# controller_rev4_3_flat.net
KiCad netlist of a schematic drawn in EAGLE
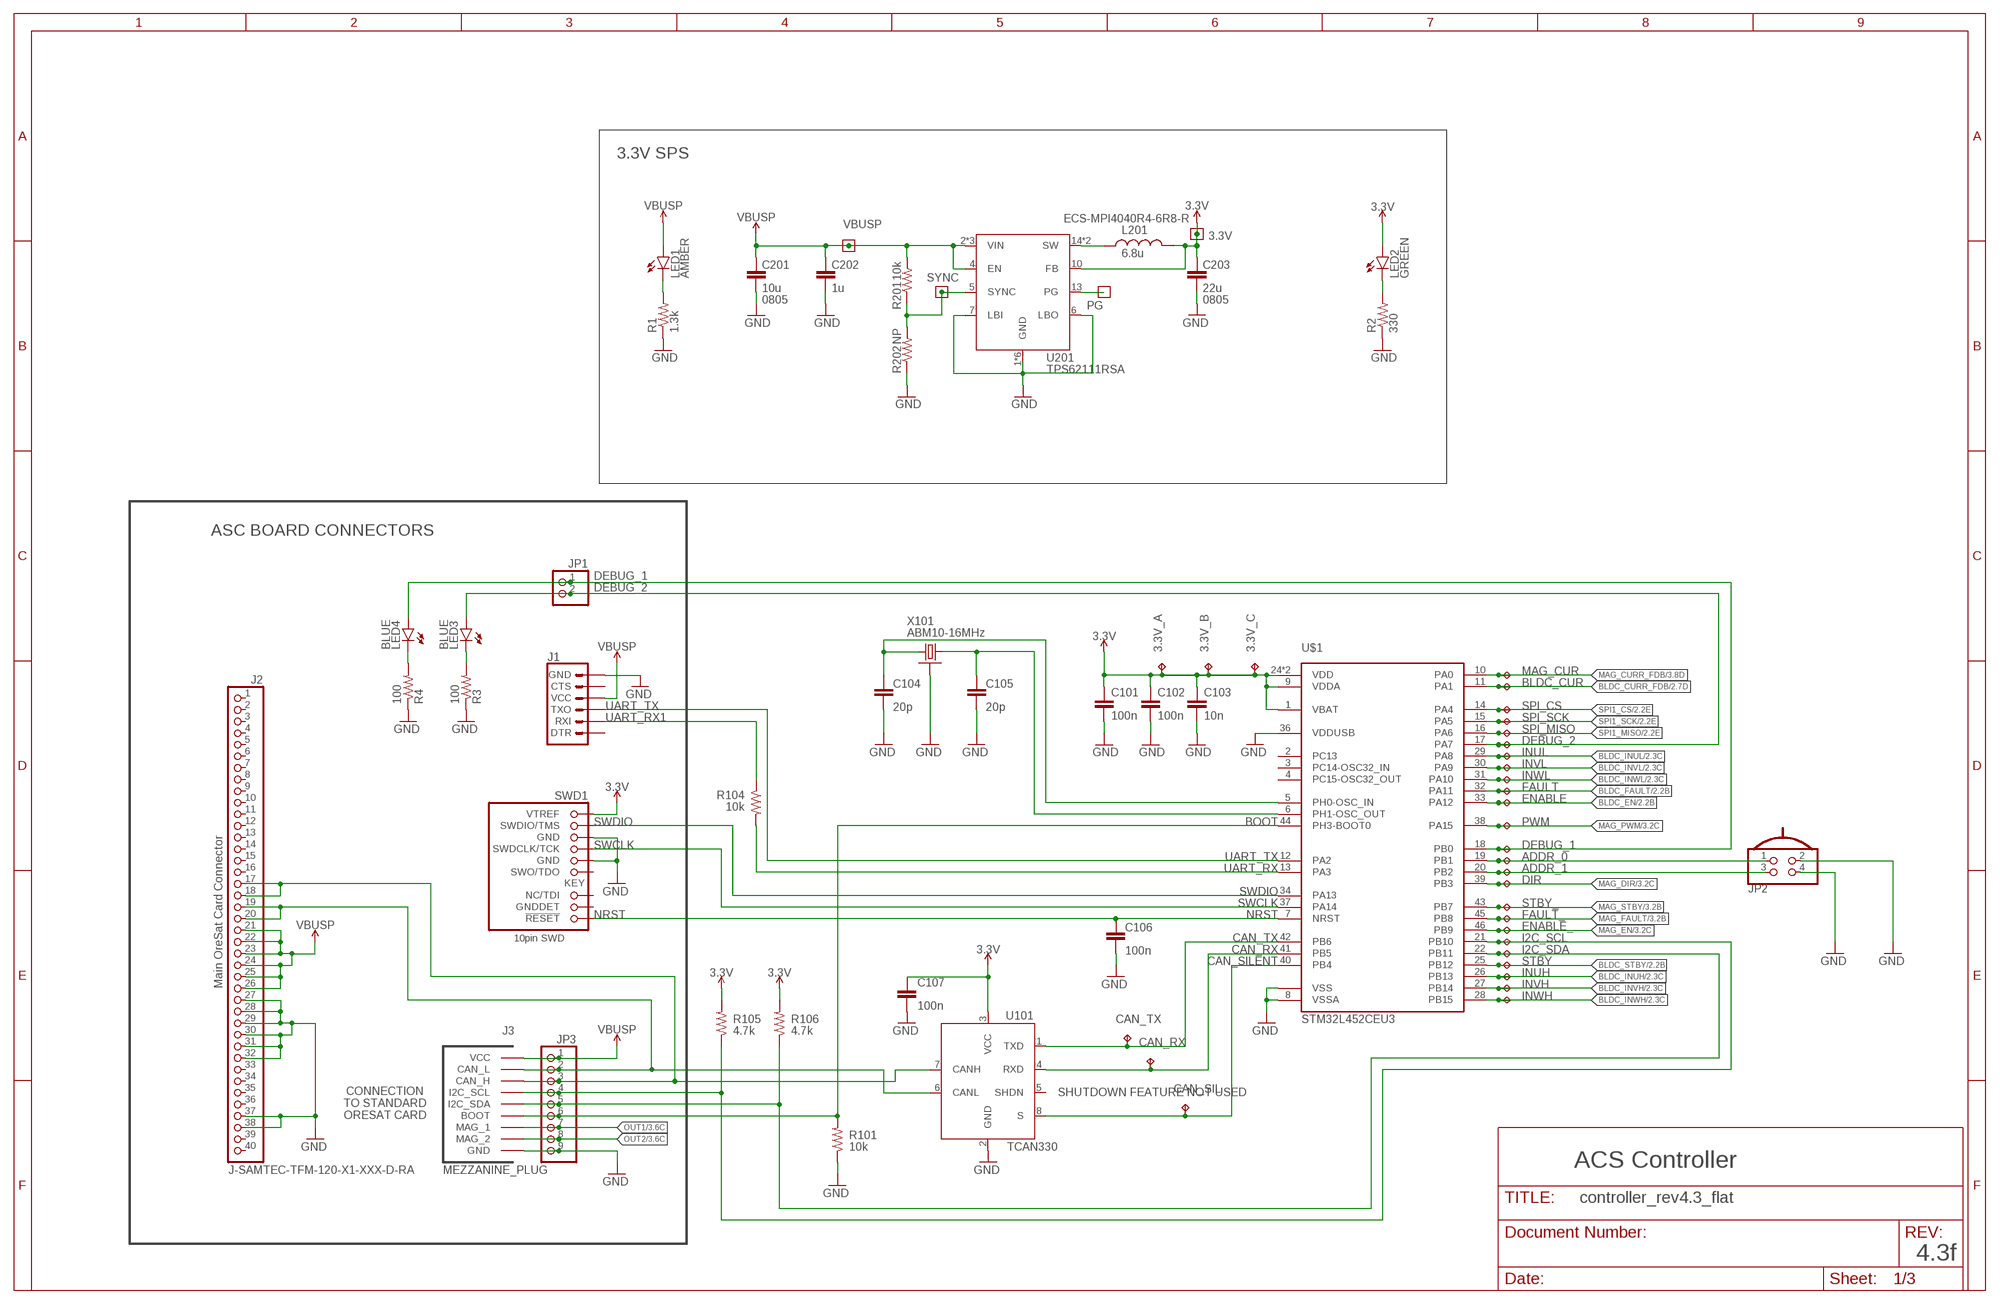
[diagram p0: schematic, sheet 1]
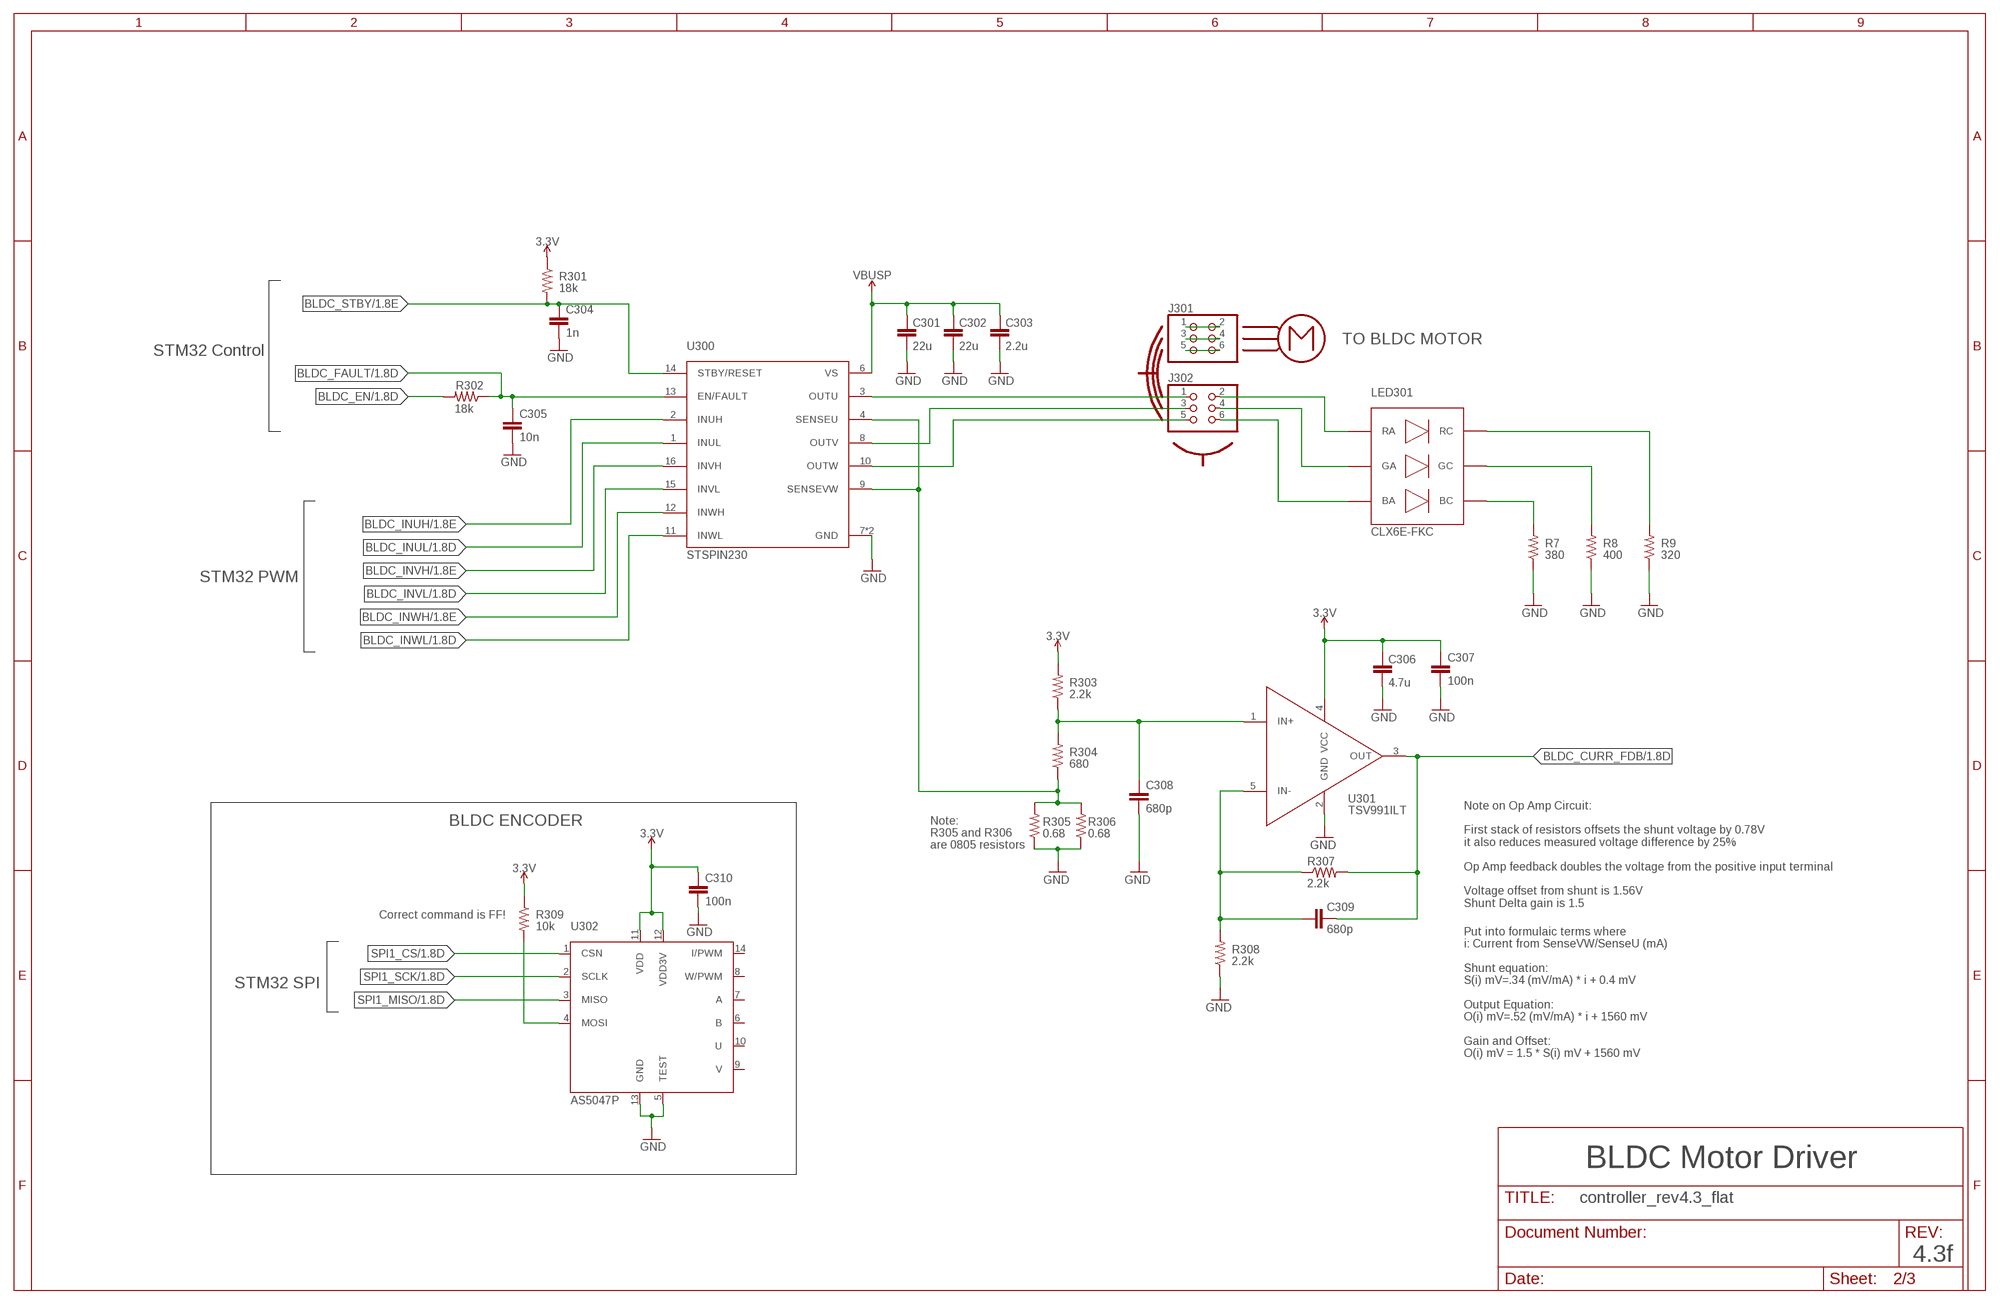
[diagram p1: schematic, sheet 2]
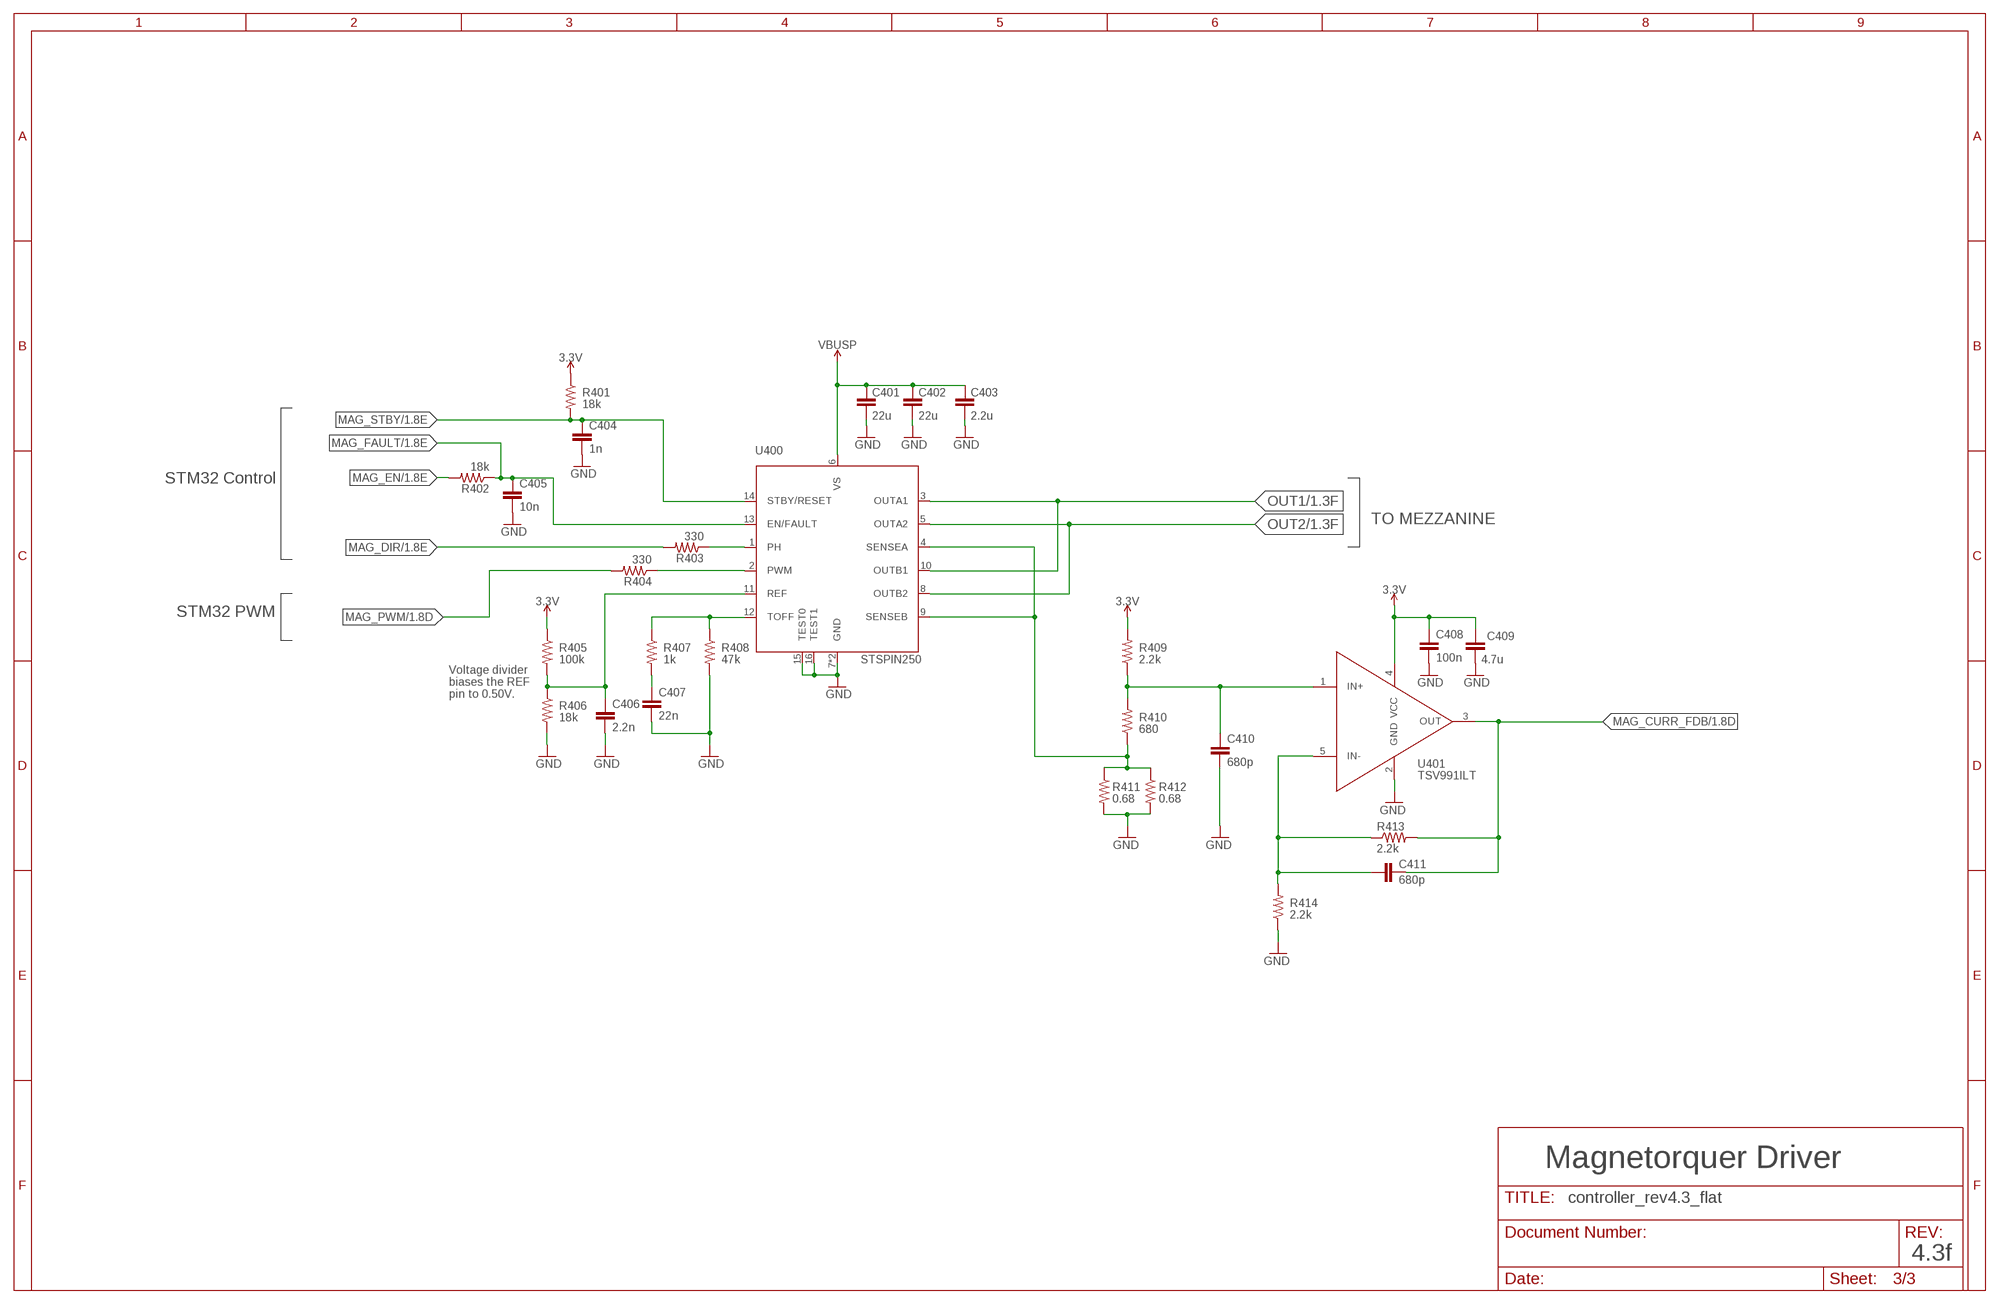
[diagram p2: schematic, sheet 3]

(export (version "E")
  (design (tool "Eeschema 10.0.6"))
  (components
    (comp (ref "3.3V")
      (value "TEST-POINT-LARGE-SQUARE")
      (footprint "eagle-import:1X01")
      (libsource (lib "eagle-import") (part "TEST-POINT-LARGE-SQUARE"))
    )
    (comp (ref "3.3V_A")
      (value "TEST-POINT-LARGE")
      (footprint "eagle-import:1X01")
      (libsource (lib "eagle-import") (part "TEST-POINT-LARGE"))
    )
    (comp (ref "3.3V_B")
      (value "TEST-POINT-LARGE")
      (footprint "eagle-import:1X01")
      (libsource (lib "eagle-import") (part "TEST-POINT-LARGE"))
    )
    (comp (ref "3.3V_C")
      (value "TEST-POINT-LARGE")
      (footprint "eagle-import:1X01")
      (libsource (lib "eagle-import") (part "TEST-POINT-LARGE"))
    )
    (comp (ref "ADDR_0")
      (value "TEST-POINT-LARGE")
      (footprint "eagle-import:1X01")
      (libsource (lib "eagle-import") (part "TEST-POINT-LARGE"))
    )
    (comp (ref "ADDR_1")
      (value "TEST-POINT-LARGE")
      (footprint "eagle-import:1X01")
      (libsource (lib "eagle-import") (part "TEST-POINT-LARGE"))
    )
    (comp (ref "BLDC_CUR")
      (value "TEST-POINT-LARGE")
      (footprint "eagle-import:1X01")
      (libsource (lib "eagle-import") (part "TEST-POINT-LARGE"))
    )
    (comp (ref "C101")
      (value "100n")
      (footprint "eagle-import:.0402-B-NOSILK")
      (fields (field (name "MFR") "Samsung") (field (name "MPN") "CL05B104KO5NNNC"))
      (libsource (lib "eagle-import") (part "rcl_custom_C-EU0402-B-NOSILK"))
    )
    (comp (ref "C102")
      (value "100n")
      (footprint "eagle-import:.0402-B-NOSILK")
      (fields (field (name "MFR") "Samsung") (field (name "MPN") "CL05B104KO5NNNC"))
      (libsource (lib "eagle-import") (part "rcl_custom_C-EU0402-B-NOSILK"))
    )
    (comp (ref "C103")
      (value "10n")
      (footprint "eagle-import:.0402-B-NOSILK")
      (fields (field (name "MFR") "Samsung") (field (name "MPN") "CL05B104KO5NNNC"))
      (libsource (lib "eagle-import") (part "rcl_custom_C-EU0402-B-NOSILK"))
    )
    (comp (ref "C104")
      (value "20p")
      (footprint "eagle-import:.0402-B-NOSILK")
      (fields (field (name "MFR") "Samsung") (field (name "MPN") "CL05C200JB51PNC"))
      (libsource (lib "eagle-import") (part "rcl_custom_C-EU0402-B-NOSILK"))
    )
    (comp (ref "C105")
      (value "20p")
      (footprint "eagle-import:.0402-B-NOSILK")
      (fields (field (name "MFR") "Samsung") (field (name "MPN") "CL05C200JB51PNC"))
      (libsource (lib "eagle-import") (part "rcl_custom_C-EU0402-B-NOSILK"))
    )
    (comp (ref "C106")
      (value "100n")
      (footprint "eagle-import:.0402-B-NOSILK")
      (fields (field (name "MFR") "Samsung") (field (name "MPN") "CL05C200JB51PNC"))
      (libsource (lib "eagle-import") (part "rcl_custom_C-EU0402-B-NOSILK"))
    )
    (comp (ref "C107")
      (value "100n")
      (footprint "eagle-import:.0402-B-NOSILK")
      (fields (field (name "MFR") "Samsung") (field (name "MPN") "CL05B104KO5NNNC"))
      (libsource (lib "eagle-import") (part "rcl_custom_C-EU0402-B-NOSILK"))
    )
    (comp (ref "C201")
      (value "10u")
      (footprint "eagle-import:.0805-B-NOSILK")
      (fields (field (name "MFR") "Samsung") (field (name "MPN") "CL21B106KOQNNNG"))
      (libsource (lib "eagle-import") (part "C-EU0805-B-NOSILK"))
    )
    (comp (ref "C202")
      (value "1u")
      (footprint "eagle-import:.0603-C-NOSILK")
      (fields (field (name "MFR") "Yageo") (field (name "MPN") "CC0603KRX5R7BB105"))
      (libsource (lib "eagle-import") (part "C-EU0603-C-NOSILK"))
    )
    (comp (ref "C203")
      (value "22u")
      (footprint "eagle-import:.0805-B-NOSILK")
      (fields (field (name "MFR") "Murata") (field (name "MPN") "GRM21BD71A226ME44L"))
      (libsource (lib "eagle-import") (part "C-EU0805-B-NOSILK"))
    )
    (comp (ref "CAN_RX")
      (value "TEST-POINT-LARGE")
      (footprint "eagle-import:1X01")
      (libsource (lib "eagle-import") (part "TEST-POINT-LARGE"))
    )
    (comp (ref "CAN_SIL")
      (value "TEST-POINT-LARGE")
      (footprint "eagle-import:1X01")
      (libsource (lib "eagle-import") (part "TEST-POINT-LARGE"))
    )
    (comp (ref "CAN_TX")
      (value "TEST-POINT-LARGE")
      (footprint "eagle-import:1X01")
      (libsource (lib "eagle-import") (part "TEST-POINT-LARGE"))
    )
    (comp (ref "DEBUG_1")
      (value "TEST-POINT-LARGE")
      (footprint "eagle-import:1X01")
      (libsource (lib "eagle-import") (part "TEST-POINT-LARGE"))
    )
    (comp (ref "DEBUG_2")
      (value "TEST-POINT-LARGE")
      (footprint "eagle-import:1X01")
      (libsource (lib "eagle-import") (part "TEST-POINT-LARGE"))
    )
    (comp (ref "DIR")
      (value "TEST-POINT-LARGE")
      (footprint "eagle-import:1X01")
      (libsource (lib "eagle-import") (part "TEST-POINT-LARGE"))
    )
    (comp (ref "ENABLE")
      (value "TEST-POINT-LARGE")
      (footprint "eagle-import:1X01")
      (libsource (lib "eagle-import") (part "TEST-POINT-LARGE"))
    )
    (comp (ref "ENABLE_")
      (value "TEST-POINT-LARGE")
      (footprint "eagle-import:1X01")
      (libsource (lib "eagle-import") (part "TEST-POINT-LARGE"))
    )
    (comp (ref "FAULT")
      (value "TEST-POINT-LARGE")
      (footprint "eagle-import:1X01")
      (libsource (lib "eagle-import") (part "TEST-POINT-LARGE"))
    )
    (comp (ref "FAULT_")
      (value "TEST-POINT-LARGE")
      (footprint "eagle-import:1X01")
      (libsource (lib "eagle-import") (part "TEST-POINT-LARGE"))
    )
    (comp (ref "I2C_SCL")
      (value "TEST-POINT-LARGE")
      (footprint "eagle-import:1X01")
      (libsource (lib "eagle-import") (part "TEST-POINT-LARGE"))
    )
    (comp (ref "I2C_SDA")
      (value "TEST-POINT-LARGE")
      (footprint "eagle-import:1X01")
      (libsource (lib "eagle-import") (part "TEST-POINT-LARGE"))
    )
    (comp (ref "INUH")
      (value "TEST-POINT-LARGE")
      (footprint "eagle-import:1X01")
      (libsource (lib "eagle-import") (part "TEST-POINT-LARGE"))
    )
    (comp (ref "INUL")
      (value "TEST-POINT-LARGE")
      (footprint "eagle-import:1X01")
      (libsource (lib "eagle-import") (part "TEST-POINT-LARGE"))
    )
    (comp (ref "INVH")
      (value "TEST-POINT-LARGE")
      (footprint "eagle-import:1X01")
      (libsource (lib "eagle-import") (part "TEST-POINT-LARGE"))
    )
    (comp (ref "INVL")
      (value "TEST-POINT-LARGE")
      (footprint "eagle-import:1X01")
      (libsource (lib "eagle-import") (part "TEST-POINT-LARGE"))
    )
    (comp (ref "INWH")
      (value "TEST-POINT-LARGE")
      (footprint "eagle-import:1X01")
      (libsource (lib "eagle-import") (part "TEST-POINT-LARGE"))
    )
    (comp (ref "INWL")
      (value "TEST-POINT-LARGE")
      (footprint "eagle-import:1X01")
      (libsource (lib "eagle-import") (part "TEST-POINT-LARGE"))
    )
    (comp (ref "J1")
      (value "6_PIN_SERIAL_TARGETSILK")
      (footprint "eagle-import:6_PIN_SERIAL_TARGET_SIDE_W_SILK")
      (libsource (lib "eagle-import") (part "6_PIN_SERIAL_TARGETSILK"))
    )
    (comp (ref "J2")
      (value "J-SAMTEC-TFM-120-X1-XXX-D-RA")
      (footprint "eagle-import:J-SAMTEC-TFM-120-X1-XXX-D-RA")
      (description "90 degree 40 pos conn header")
      (fields (field (name "MFG") "Samtec Inc."))
      (libsource (lib "eagle-import") (part "J-SAMTEC-TFM-120-X1-XXX-D-RA"))
    )
    (comp (ref "J3")
      (value "MEZZANINE_PLUG")
      (footprint "eagle-import:MEZZANINE_PLUG")
      (fields (field (name "MFG") "Molex"))
      (libsource (lib "eagle-import") (part "MEZZANINE_PLUG"))
    )
    (comp (ref "JP1")
      (value "PINHD-1X2")
      (footprint "eagle-import:1X02")
      (libsource (lib "eagle-import") (part "PINHD-1X2"))
    )
    (comp (ref "JP2")
      (value "PINHD-2X2")
      (footprint "eagle-import:2X02")
      (description "2x2 .1 inch pin header")
      (fields (field (name "MFG") "Harwin Inc."))
      (libsource (lib "eagle-import") (part "PINHD-2X2"))
    )
    (comp (ref "JP3")
      (value "PINHD-1X9")
      (footprint "eagle-import:1X09")
      (libsource (lib "eagle-import") (part "PINHD-1X9"))
    )
    (comp (ref "L201")
      (value "6.8u")
      (footprint "eagle-import:ECS-MPI4040")
      (fields (field (name "MFR") "ECS") (field (name "MPN") "ECS-MPI4040R4-6R8-R"))
      (libsource (lib "eagle-import") (part "L-ECS-MPI4040"))
    )
    (comp (ref "LED1")
      (value "AMBER")
      (footprint "eagle-import:CHIPLED_0603")
      (libsource (lib "eagle-import") (part "LEDCHIPLED_0603"))
    )
    (comp (ref "LED2")
      (value "GREEN")
      (footprint "eagle-import:CHIPLED_0603")
      (libsource (lib "eagle-import") (part "LEDCHIPLED_0603"))
    )
    (comp (ref "LED3")
      (value "BLUE")
      (footprint "eagle-import:CHIPLED_0603")
      (libsource (lib "eagle-import") (part "LEDCHIPLED_0603"))
    )
    (comp (ref "LED4")
      (value "BLUE")
      (footprint "eagle-import:CHIPLED_0603")
      (libsource (lib "eagle-import") (part "LEDCHIPLED_0603"))
    )
    (comp (ref "MAG_CUR")
      (value "TEST-POINT-LARGE")
      (footprint "eagle-import:1X01")
      (libsource (lib "eagle-import") (part "TEST-POINT-LARGE"))
    )
    (comp (ref "PG")
      (value "TEST-POINT-LARGE-SQUARE")
      (footprint "eagle-import:1X01")
      (libsource (lib "eagle-import") (part "TEST-POINT-LARGE-SQUARE"))
    )
    (comp (ref "PWM")
      (value "TEST-POINT-LARGE")
      (footprint "eagle-import:1X01")
      (libsource (lib "eagle-import") (part "TEST-POINT-LARGE"))
    )
    (comp (ref "R1")
      (value "1.3k")
      (footprint "eagle-import:.0402-B-NOSILK")
      (libsource (lib "eagle-import") (part "R-US_0402-B-NOSILK"))
    )
    (comp (ref "R2")
      (value "330")
      (footprint "eagle-import:.0402-B-NOSILK")
      (libsource (lib "eagle-import") (part "R-US_0402-B-NOSILK"))
    )
    (comp (ref "R3")
      (value "100")
      (footprint "eagle-import:.0402-B-NOSILK")
      (libsource (lib "eagle-import") (part "R-US_0402-B-NOSILK"))
    )
    (comp (ref "R4")
      (value "100")
      (footprint "eagle-import:.0402-B-NOSILK")
      (libsource (lib "eagle-import") (part "R-US_0402-B-NOSILK"))
    )
    (comp (ref "R101")
      (value "10k")
      (footprint "eagle-import:.0402-B-NOSILK")
      (fields (field (name "MFR") "Samsung") (field (name "MPN") "RC1005F6653CS"))
      (libsource (lib "eagle-import") (part "rcl_custom_R-US_0402-B-NOSILK"))
    )
    (comp (ref "R104")
      (value "10k")
      (footprint "eagle-import:.0402-B-NOSILK")
      (fields (field (name "MFR") "Samsung") (field (name "MPN") "RC1005F6653CS"))
      (libsource (lib "eagle-import") (part "rcl_custom_R-US_0402-B-NOSILK"))
    )
    (comp (ref "R105")
      (value "4.7k")
      (footprint "eagle-import:.0402-B-NOSILK")
      (fields (field (name "MFR") "Samsung") (field (name "MPN") "RC1005F6653CS"))
      (libsource (lib "eagle-import") (part "rcl_custom_R-US_0402-B-NOSILK"))
    )
    (comp (ref "R106")
      (value "4.7k")
      (footprint "eagle-import:.0402-B-NOSILK")
      (fields (field (name "MFR") "Samsung") (field (name "MPN") "RC1005F6653CS"))
      (libsource (lib "eagle-import") (part "rcl_custom_R-US_0402-B-NOSILK"))
    )
    (comp (ref "R201")
      (value "10k")
      (footprint "eagle-import:.0603-C-NOSILK")
      (fields (field (name "MFR") "Stackpole") (field (name "MPN") "RNCP0603FTD10K0"))
      (libsource (lib "eagle-import") (part "R-US_0603-C-NOSILK"))
    )
    (comp (ref "R202")
      (value "NP")
      (footprint "eagle-import:.0603-C-NOSILK")
      (fields (field (name "MFR") "Samsung") (field (name "MPN") "RC1005F6653CS"))
      (libsource (lib "eagle-import") (part "R-US_0603-C-NOSILK"))
    )
    (comp (ref "SPI_CS")
      (value "TEST-POINT-LARGE")
      (footprint "eagle-import:1X01")
      (libsource (lib "eagle-import") (part "TEST-POINT-LARGE"))
    )
    (comp (ref "SPI_MISO")
      (value "TEST-POINT-LARGE")
      (footprint "eagle-import:1X01")
      (libsource (lib "eagle-import") (part "TEST-POINT-LARGE"))
    )
    (comp (ref "SPI_SCK")
      (value "TEST-POINT-LARGE")
      (footprint "eagle-import:1X01")
      (libsource (lib "eagle-import") (part "TEST-POINT-LARGE"))
    )
    (comp (ref "STBY")
      (value "TEST-POINT-LARGE")
      (footprint "eagle-import:1X01")
      (libsource (lib "eagle-import") (part "TEST-POINT-LARGE"))
    )
    (comp (ref "STBY_")
      (value "TEST-POINT-LARGE")
      (footprint "eagle-import:1X01")
      (libsource (lib "eagle-import") (part "TEST-POINT-LARGE"))
    )
    (comp (ref "SWD1")
      (value "1.27MM-SWD-CONNECTOR")
      (footprint "eagle-import:1.27MM_2X5")
      (libsource (lib "eagle-import") (part "1.27MM-SWD-CONNECTOR"))
    )
    (comp (ref "SYNC")
      (value "TEST-POINT-LARGE-SQUARE")
      (footprint "eagle-import:1X01")
      (libsource (lib "eagle-import") (part "TEST-POINT-LARGE-SQUARE"))
    )
    (comp (ref "U$1")
      (value "STM32L452CEU3")
      (footprint "eagle-import:QFPN-48")
      (fields (field (name "MFG") "STMicroelectronics"))
      (libsource (lib "eagle-import") (part "STM32L452CEU3"))
    )
    (comp (ref "U101")
      (value "TCAN330")
      (footprint "eagle-import:SOT23-8_TI-DCN")
      (fields (field (name "MFR") "Texas Instruments") (field (name "MPN") "TCAN330GDCNT"))
      (libsource (lib "eagle-import") (part "TCAN330"))
    )
    (comp (ref "U201")
      (value "TPS62111RSA")
      (footprint "eagle-import:S-PVQFN-16")
      (fields (field (name "MFR") "Texas Instruments"))
      (libsource (lib "eagle-import") (part "TPS6211X"))
    )
    (comp (ref "VBUSP")
      (value "TEST-POINT-LARGE-SQUARE")
      (footprint "eagle-import:1X01")
      (libsource (lib "eagle-import") (part "TEST-POINT-LARGE-SQUARE"))
    )
    (comp (ref "X101")
      (value "ABM10-16MHz")
      (footprint "eagle-import:CRYSTAL_2.5X2")
      (fields (field (name "MFR") "ECS Inc.") (field (name "MPN") "ECS-160-10-36Q-ES-TR"))
      (libsource (lib "eagle-import") (part "CRYSTAL-WITH-GND"))
    )
    (comp (ref "C301")
      (value "22u")
      (footprint "eagle-import:.0603-B-NOSILK")
      (fields (field (name "MFR") "Samsung") (field (name "MPN") "CL05B104KO5NNNC"))
      (libsource (lib "eagle-import") (part "C-EU0603-B-NOSILK"))
    )
    (comp (ref "C302")
      (value "22u")
      (footprint "eagle-import:.0603-B-NOSILK")
      (fields (field (name "MFR") "Samsung") (field (name "MPN") "CL05B104KO5NNNC"))
      (libsource (lib "eagle-import") (part "C-EU0603-B-NOSILK"))
    )
    (comp (ref "C303")
      (value "2.2u")
      (footprint "eagle-import:.0603-B-NOSILK")
      (fields (field (name "MFR") "Samsung") (field (name "MPN") "CL05B104KO5NNNC"))
      (libsource (lib "eagle-import") (part "C-EU0603-B-NOSILK"))
    )
    (comp (ref "C304")
      (value "1n")
      (footprint "eagle-import:.0402-B-NOSILK")
      (fields (field (name "MFR") "Samsung") (field (name "MPN") "CL05B104KO5NNNC"))
      (libsource (lib "eagle-import") (part "rcl_custom_C-EU0402-B-NOSILK"))
    )
    (comp (ref "C305")
      (value "10n")
      (footprint "eagle-import:.0402-B-NOSILK")
      (fields (field (name "MFR") "Samsung") (field (name "MPN") "CL05B104KO5NNNC"))
      (libsource (lib "eagle-import") (part "rcl_custom_C-EU0402-B-NOSILK"))
    )
    (comp (ref "C306")
      (value "4.7u")
      (footprint "eagle-import:.0603-B-NOSILK")
      (fields (field (name "MFR") "Samsung") (field (name "MPN") "CL05B104KO5NNNC"))
      (libsource (lib "eagle-import") (part "C-EU0603-B-NOSILK"))
    )
    (comp (ref "C307")
      (value "100n")
      (footprint "eagle-import:.0402-B-NOSILK")
      (fields (field (name "MFR") "Samsung") (field (name "MPN") "CL05B104KO5NNNC"))
      (libsource (lib "eagle-import") (part "rcl_custom_C-EU0402-B-NOSILK"))
    )
    (comp (ref "C308")
      (value "680p")
      (footprint "eagle-import:.0402-B-NOSILK")
      (fields (field (name "MFR") "Samsung") (field (name "MPN") "CL05B104KO5NNNC"))
      (libsource (lib "eagle-import") (part "rcl_custom_C-EU0402-B-NOSILK"))
    )
    (comp (ref "C309")
      (value "680p")
      (footprint "eagle-import:.0402-B-NOSILK")
      (fields (field (name "MFR") "Samsung") (field (name "MPN") "CL05B104KO5NNNC"))
      (libsource (lib "eagle-import") (part "rcl_custom_C-EU0402-B-NOSILK"))
    )
    (comp (ref "C310")
      (value "100n")
      (footprint "eagle-import:.0402-B-NOSILK")
      (fields (field (name "MFR") "Samsung") (field (name "MPN") "CL05B104KO5NNNC"))
      (libsource (lib "eagle-import") (part "rcl_custom_C-EU0402-B-NOSILK"))
    )
    (comp (ref "J301")
      (value "PINHD-2X3")
      (footprint "eagle-import:2X03")
      (libsource (lib "eagle-import") (part "PINHD-2X3"))
    )
    (comp (ref "J302")
      (value "PINHD-2X3")
      (footprint "eagle-import:2X03")
      (libsource (lib "eagle-import") (part "PINHD-2X3"))
    )
    (comp (ref "LED301")
      (value "CLX6E-FKC")
      (footprint "eagle-import:CLX6E-FKC")
      (libsource (lib "eagle-import") (part "CLX6E-FKC"))
    )
    (comp (ref "R7")
      (value "380")
      (footprint "eagle-import:.0402-B-NOSILK")
      (fields (field (name "MFR") "Samsung") (field (name "MPN") "RC1005F6653CS"))
      (libsource (lib "eagle-import") (part "rcl_custom_R-US_0402-B-NOSILK"))
    )
    (comp (ref "R8")
      (value "400")
      (footprint "eagle-import:.0402-B-NOSILK")
      (fields (field (name "MFR") "Samsung") (field (name "MPN") "RC1005F6653CS"))
      (libsource (lib "eagle-import") (part "rcl_custom_R-US_0402-B-NOSILK"))
    )
    (comp (ref "R9")
      (value "320")
      (footprint "eagle-import:.0402-B-NOSILK")
      (fields (field (name "MFR") "Samsung") (field (name "MPN") "RC1005F6653CS"))
      (libsource (lib "eagle-import") (part "rcl_custom_R-US_0402-B-NOSILK"))
    )
    (comp (ref "R301")
      (value "18k")
      (footprint "eagle-import:.0402-B-NOSILK")
      (fields (field (name "MFR") "Samsung") (field (name "MPN") "RC1005F6653CS"))
      (libsource (lib "eagle-import") (part "rcl_custom_R-US_0402-B-NOSILK"))
    )
    (comp (ref "R302")
      (value "18k")
      (footprint "eagle-import:.0402-B-NOSILK")
      (fields (field (name "MFR") "Samsung") (field (name "MPN") "RC1005F6653CS"))
      (libsource (lib "eagle-import") (part "rcl_custom_R-US_0402-B-NOSILK"))
    )
    (comp (ref "R303")
      (value "2.2k")
      (footprint "eagle-import:.0402-B-NOSILK")
      (fields (field (name "MFR") "Samsung") (field (name "MPN") "RC1005F6653CS"))
      (libsource (lib "eagle-import") (part "rcl_custom_R-US_0402-B-NOSILK"))
    )
    (comp (ref "R304")
      (value "680")
      (footprint "eagle-import:.0402-B-NOSILK")
      (fields (field (name "MFR") "Samsung") (field (name "MPN") "RC1005F6653CS"))
      (libsource (lib "eagle-import") (part "rcl_custom_R-US_0402-B-NOSILK"))
    )
    (comp (ref "R305")
      (value "0.68")
      (footprint "eagle-import:.0805-B-NOSILK")
      (libsource (lib "eagle-import") (part "R-US_0805-B-NOSILK"))
    )
    (comp (ref "R306")
      (value "0.68")
      (footprint "eagle-import:.0805-B-NOSILK")
      (libsource (lib "eagle-import") (part "R-US_0805-B-NOSILK"))
    )
    (comp (ref "R307")
      (value "2.2k")
      (footprint "eagle-import:.0402-B-NOSILK")
      (fields (field (name "MFR") "Samsung") (field (name "MPN") "RC1005F6653CS"))
      (libsource (lib "eagle-import") (part "rcl_custom_R-US_0402-B-NOSILK"))
    )
    (comp (ref "R308")
      (value "2.2k")
      (footprint "eagle-import:.0402-B-NOSILK")
      (fields (field (name "MFR") "Samsung") (field (name "MPN") "RC1005F6653CS"))
      (libsource (lib "eagle-import") (part "rcl_custom_R-US_0402-B-NOSILK"))
    )
    (comp (ref "R309")
      (value "10k")
      (footprint "eagle-import:.0402-B-NOSILK")
      (fields (field (name "MFR") "Samsung") (field (name "MPN") "RC1005F6653CS"))
      (libsource (lib "eagle-import") (part "rcl_custom_R-US_0402-B-NOSILK"))
    )
    (comp (ref "U300")
      (value "STSPIN230")
      (footprint "eagle-import:VFQPN")
      (fields (field (name "MFG") "STMicroelectronics"))
      (libsource (lib "eagle-import") (part "STSPIN230"))
    )
    (comp (ref "U301")
      (value "TSV991ILT")
      (footprint "eagle-import:SOT23-5")
      (fields (field (name "MFG") "STMicroelectronics"))
      (libsource (lib "eagle-import") (part "TSV991ILT"))
    )
    (comp (ref "U302")
      (value "AS5047P")
      (footprint "eagle-import:TSSOP14")
      (fields (field (name "MFG") "ams"))
      (libsource (lib "eagle-import") (part "AS5047P"))
    )
    (comp (ref "C401")
      (value "22u")
      (footprint "eagle-import:.0603-B-NOSILK")
      (fields (field (name "MFR") "Samsung") (field (name "MPN") "CL05B104KO5NNNC"))
      (libsource (lib "eagle-import") (part "C-EU0603-B-NOSILK"))
    )
    (comp (ref "C402")
      (value "22u")
      (footprint "eagle-import:.0603-B-NOSILK")
      (fields (field (name "MFR") "Samsung") (field (name "MPN") "CL05B104KO5NNNC"))
      (libsource (lib "eagle-import") (part "C-EU0603-B-NOSILK"))
    )
    (comp (ref "C403")
      (value "2.2u")
      (footprint "eagle-import:.0603-B-NOSILK")
      (fields (field (name "MFR") "Samsung") (field (name "MPN") "CL05B104KO5NNNC"))
      (libsource (lib "eagle-import") (part "C-EU0603-B-NOSILK"))
    )
    (comp (ref "C404")
      (value "1n")
      (footprint "eagle-import:.0402-B-NOSILK")
      (fields (field (name "MFR") "Samsung") (field (name "MPN") "CL05B104KO5NNNC"))
      (libsource (lib "eagle-import") (part "rcl_custom_C-EU0402-B-NOSILK"))
    )
    (comp (ref "C405")
      (value "10n")
      (footprint "eagle-import:.0402-B-NOSILK")
      (fields (field (name "MFR") "Samsung") (field (name "MPN") "CL05B104KO5NNNC"))
      (libsource (lib "eagle-import") (part "rcl_custom_C-EU0402-B-NOSILK"))
    )
    (comp (ref "C406")
      (value "2.2n")
      (footprint "eagle-import:.0402-B-NOSILK")
      (fields (field (name "MFR") "Samsung") (field (name "MPN") "CL05B104KO5NNNC"))
      (libsource (lib "eagle-import") (part "rcl_custom_C-EU0402-B-NOSILK"))
    )
    (comp (ref "C407")
      (value "22n")
      (footprint "eagle-import:.0402-B-NOSILK")
      (fields (field (name "MFR") "Samsung") (field (name "MPN") "CL05B104KO5NNNC"))
      (libsource (lib "eagle-import") (part "rcl_custom_C-EU0402-B-NOSILK"))
    )
    (comp (ref "C408")
      (value "100n")
      (footprint "eagle-import:.0402-B-NOSILK")
      (fields (field (name "MFR") "Samsung") (field (name "MPN") "CL05B104KO5NNNC"))
      (libsource (lib "eagle-import") (part "rcl_custom_C-EU0402-B-NOSILK"))
    )
    (comp (ref "C409")
      (value "4.7u")
      (footprint "eagle-import:.0603-B-NOSILK")
      (fields (field (name "MFR") "Samsung") (field (name "MPN") "CL05B104KO5NNNC"))
      (libsource (lib "eagle-import") (part "C-EU0603-B-NOSILK"))
    )
    (comp (ref "C410")
      (value "680p")
      (footprint "eagle-import:.0402-B-NOSILK")
      (fields (field (name "MFR") "Samsung") (field (name "MPN") "CL05B104KO5NNNC"))
      (libsource (lib "eagle-import") (part "rcl_custom_C-EU0402-B-NOSILK"))
    )
    (comp (ref "C411")
      (value "680p")
      (footprint "eagle-import:.0402-B-NOSILK")
      (fields (field (name "MFR") "Samsung") (field (name "MPN") "CL05B104KO5NNNC"))
      (libsource (lib "eagle-import") (part "rcl_custom_C-EU0402-B-NOSILK"))
    )
    (comp (ref "R401")
      (value "18k")
      (footprint "eagle-import:.0402-B-NOSILK")
      (fields (field (name "MFR") "Samsung") (field (name "MPN") "RC1005F6653CS"))
      (libsource (lib "eagle-import") (part "rcl_custom_R-US_0402-B-NOSILK"))
    )
    (comp (ref "R402")
      (value "18k")
      (footprint "eagle-import:.0402-B-NOSILK")
      (fields (field (name "MFR") "Samsung") (field (name "MPN") "RC1005F6653CS"))
      (libsource (lib "eagle-import") (part "rcl_custom_R-US_0402-B-NOSILK"))
    )
    (comp (ref "R403")
      (value "330")
      (footprint "eagle-import:.0402-B-NOSILK")
      (fields (field (name "MFR") "Samsung") (field (name "MPN") "RC1005F6653CS"))
      (libsource (lib "eagle-import") (part "rcl_custom_R-US_0402-B-NOSILK"))
    )
    (comp (ref "R404")
      (value "330")
      (footprint "eagle-import:.0402-B-NOSILK")
      (fields (field (name "MFR") "Samsung") (field (name "MPN") "RC1005F6653CS"))
      (libsource (lib "eagle-import") (part "rcl_custom_R-US_0402-B-NOSILK"))
    )
    (comp (ref "R405")
      (value "100k")
      (footprint "eagle-import:.0402-B-NOSILK")
      (fields (field (name "MFR") "Samsung") (field (name "MPN") "RC1005F6653CS"))
      (libsource (lib "eagle-import") (part "rcl_custom_R-US_0402-B-NOSILK"))
    )
    (comp (ref "R406")
      (value "18k")
      (footprint "eagle-import:.0402-B-NOSILK")
      (fields (field (name "MFR") "Samsung") (field (name "MPN") "RC1005F6653CS"))
      (libsource (lib "eagle-import") (part "rcl_custom_R-US_0402-B-NOSILK"))
    )
    (comp (ref "R407")
      (value "1k")
      (footprint "eagle-import:.0402-B-NOSILK")
      (fields (field (name "MFR") "Samsung") (field (name "MPN") "RC1005F6653CS"))
      (libsource (lib "eagle-import") (part "rcl_custom_R-US_0402-B-NOSILK"))
    )
    (comp (ref "R408")
      (value "47k")
      (footprint "eagle-import:.0402-B-NOSILK")
      (fields (field (name "MFR") "Samsung") (field (name "MPN") "RC1005F6653CS"))
      (libsource (lib "eagle-import") (part "rcl_custom_R-US_0402-B-NOSILK"))
    )
    (comp (ref "R409")
      (value "2.2k")
      (footprint "eagle-import:.0402-B-NOSILK")
      (fields (field (name "MFR") "Samsung") (field (name "MPN") "RC1005F6653CS"))
      (libsource (lib "eagle-import") (part "rcl_custom_R-US_0402-B-NOSILK"))
    )
    (comp (ref "R410")
      (value "680")
      (footprint "eagle-import:.0402-B-NOSILK")
      (fields (field (name "MFR") "Samsung") (field (name "MPN") "RC1005F6653CS"))
      (libsource (lib "eagle-import") (part "rcl_custom_R-US_0402-B-NOSILK"))
    )
    (comp (ref "R411")
      (value "0.68")
      (footprint "eagle-import:.0805-B-NOSILK")
      (libsource (lib "eagle-import") (part "R-US_0805-B-NOSILK"))
    )
    (comp (ref "R412")
      (value "0.68")
      (footprint "eagle-import:.0805-B-NOSILK")
      (libsource (lib "eagle-import") (part "R-US_0805-B-NOSILK"))
    )
    (comp (ref "R413")
      (value "2.2k")
      (footprint "eagle-import:.0402-B-NOSILK")
      (fields (field (name "MFR") "Samsung") (field (name "MPN") "RC1005F6653CS"))
      (libsource (lib "eagle-import") (part "rcl_custom_R-US_0402-B-NOSILK"))
    )
    (comp (ref "R414")
      (value "2.2k")
      (footprint "eagle-import:.0402-B-NOSILK")
      (fields (field (name "MFR") "Samsung") (field (name "MPN") "RC1005F6653CS"))
      (libsource (lib "eagle-import") (part "rcl_custom_R-US_0402-B-NOSILK"))
    )
    (comp (ref "U400")
      (value "STSPIN250")
      (footprint "eagle-import:VFQPN")
      (fields (field (name "MFG") "STMicroelectronics"))
      (libsource (lib "eagle-import") (part "STSPIN250"))
    )
    (comp (ref "U401")
      (value "TSV991ILT")
      (footprint "eagle-import:SOT23-5")
      (fields (field (name "MFG") "STMicroelectronics"))
      (libsource (lib "eagle-import") (part "TSV991ILT"))
    )
  )
  (nets
    (net (code "1") (name "3.3V") (class "Default")
      (node (ref "3.3V") (pin "1") (pinfunction "1_1") (pintype "passive"))
      (node (ref "3.3V_A") (pin "1") (pinfunction "TP_1") (pintype "input"))
      (node (ref "3.3V_B") (pin "1") (pinfunction "TP_1") (pintype "input"))
      (node (ref "3.3V_C") (pin "1") (pinfunction "TP_1") (pintype "input"))
      (node (ref "C101") (pin "1") (pinfunction "1_1") (pintype "passive"))
      (node (ref "C102") (pin "1") (pinfunction "1_1") (pintype "passive"))
      (node (ref "C103") (pin "1") (pinfunction "1_1") (pintype "passive"))
      (node (ref "C107") (pin "1") (pinfunction "1_1") (pintype "passive"))
      (node (ref "C203") (pin "1") (pinfunction "1_1") (pintype "passive"))
      (node (ref "C306") (pin "1") (pinfunction "1_1") (pintype "passive"))
      (node (ref "C307") (pin "1") (pinfunction "1_1") (pintype "passive"))
      (node (ref "C310") (pin "1") (pinfunction "1_1") (pintype "passive"))
      (node (ref "C408") (pin "1") (pinfunction "1_1") (pintype "passive"))
      (node (ref "C409") (pin "1") (pinfunction "1_1") (pintype "passive"))
      (node (ref "L201") (pin "2") (pinfunction "2_2") (pintype "passive"))
      (node (ref "LED2") (pin "A") (pinfunction "A_A") (pintype "passive"))
      (node (ref "R105") (pin "2") (pinfunction "2_2") (pintype "passive"))
      (node (ref "R106") (pin "2") (pinfunction "2_2") (pintype "passive"))
      (node (ref "R301") (pin "1") (pinfunction "1_1") (pintype "passive"))
      (node (ref "R303") (pin "2") (pinfunction "2_2") (pintype "passive"))
      (node (ref "R309") (pin "1") (pinfunction "1_1") (pintype "passive"))
      (node (ref "R401") (pin "1") (pinfunction "1_1") (pintype "passive"))
      (node (ref "R405") (pin "1") (pinfunction "1_1") (pintype "passive"))
      (node (ref "R409") (pin "2") (pinfunction "2_2") (pintype "passive"))
      (node (ref "SWD1") (pin "VTREF") (pinfunction "VTREF_VTREF") (pintype "passive"))
      (node (ref "U$1") (pin "1") (pinfunction "VBAT_1") (pintype "bidirectional"))
      (node (ref "U$1") (pin "24") (pinfunction "VDD_24") (pintype "bidirectional"))
      (node (ref "U$1") (pin "48") (pinfunction "VDD_48") (pintype "bidirectional"))
      (node (ref "U$1") (pin "9") (pinfunction "VDDA_9") (pintype "bidirectional"))
      (node (ref "U101") (pin "3") (pinfunction "VCC_3") (pintype "power_in"))
      (node (ref "U201") (pin "10") (pinfunction "FB_10") (pintype "input"))
      (node (ref "U301") (pin "4") (pinfunction "VCC_4") (pintype "bidirectional"))
      (node (ref "U302") (pin "11") (pinfunction "VDD_11") (pintype "power_in"))
      (node (ref "U302") (pin "12") (pinfunction "VDD3V_12") (pintype "power_in"))
      (node (ref "U401") (pin "4") (pinfunction "VCC_4") (pintype "bidirectional"))
    )
    (net (code "2") (name "BLDC_CURR_FDB") (class "Default")
      (node (ref "BLDC_CUR") (pin "1") (pinfunction "TP_1") (pintype "input"))
      (node (ref "C309") (pin "1") (pinfunction "1_1") (pintype "passive"))
      (node (ref "R307") (pin "2") (pinfunction "2_2") (pintype "passive"))
      (node (ref "U$1") (pin "11") (pinfunction "PA1_11") (pintype "bidirectional"))
      (node (ref "U301") (pin "3") (pinfunction "OUT_3") (pintype "bidirectional"))
    )
    (net (code "3") (name "BLDC_EN") (class "Default")
      (node (ref "ENABLE") (pin "1") (pinfunction "TP_1") (pintype "input"))
      (node (ref "R302") (pin "2") (pinfunction "2_2") (pintype "passive"))
      (node (ref "U$1") (pin "33") (pinfunction "PA12_33") (pintype "bidirectional"))
    )
    (net (code "4") (name "BLDC_FAULT") (class "Default")
      (node (ref "C305") (pin "1") (pinfunction "1_1") (pintype "passive"))
      (node (ref "FAULT") (pin "1") (pinfunction "TP_1") (pintype "input"))
      (node (ref "R302") (pin "1") (pinfunction "1_1") (pintype "passive"))
      (node (ref "U$1") (pin "32") (pinfunction "PA11_32") (pintype "bidirectional"))
      (node (ref "U300") (pin "13") (pinfunction "EN/FAULT_13") (pintype "bidirectional"))
    )
    (net (code "5") (name "BLDC_INUH") (class "Default")
      (node (ref "INUH") (pin "1") (pinfunction "TP_1") (pintype "input"))
      (node (ref "U$1") (pin "26") (pinfunction "PB13_26") (pintype "bidirectional"))
      (node (ref "U300") (pin "2") (pinfunction "INUH_2") (pintype "input"))
    )
    (net (code "6") (name "BLDC_INUL") (class "Default")
      (node (ref "INUL") (pin "1") (pinfunction "TP_1") (pintype "input"))
      (node (ref "U$1") (pin "29") (pinfunction "PA8_29") (pintype "bidirectional"))
      (node (ref "U300") (pin "1") (pinfunction "INUL_1") (pintype "input"))
    )
    (net (code "7") (name "BLDC_INVH") (class "Default")
      (node (ref "INVH") (pin "1") (pinfunction "TP_1") (pintype "input"))
      (node (ref "U$1") (pin "27") (pinfunction "PB14_27") (pintype "bidirectional"))
      (node (ref "U300") (pin "16") (pinfunction "INVH_16") (pintype "input"))
    )
    (net (code "8") (name "BLDC_INVL") (class "Default")
      (node (ref "INVL") (pin "1") (pinfunction "TP_1") (pintype "input"))
      (node (ref "U$1") (pin "30") (pinfunction "PA9_30") (pintype "bidirectional"))
      (node (ref "U300") (pin "15") (pinfunction "INVL_15") (pintype "input"))
    )
    (net (code "9") (name "BLDC_INWH") (class "Default")
      (node (ref "INWH") (pin "1") (pinfunction "TP_1") (pintype "input"))
      (node (ref "U$1") (pin "28") (pinfunction "PB15_28") (pintype "bidirectional"))
      (node (ref "U300") (pin "12") (pinfunction "INWH_12") (pintype "input"))
    )
    (net (code "10") (name "BLDC_INWL") (class "Default")
      (node (ref "INWL") (pin "1") (pinfunction "TP_1") (pintype "input"))
      (node (ref "U$1") (pin "31") (pinfunction "PA10_31") (pintype "bidirectional"))
      (node (ref "U300") (pin "11") (pinfunction "INWL_11") (pintype "input"))
    )
    (net (code "11") (name "BLDC_STBY") (class "Default")
      (node (ref "C304") (pin "1") (pinfunction "1_1") (pintype "passive"))
      (node (ref "R301") (pin "2") (pinfunction "2_2") (pintype "passive"))
      (node (ref "STBY") (pin "1") (pinfunction "TP_1") (pintype "input"))
      (node (ref "U$1") (pin "25") (pinfunction "PB12_25") (pintype "bidirectional"))
      (node (ref "U300") (pin "14") (pinfunction "STBY/RESET_14") (pintype "input"))
    )
    (net (code "12") (name "BOOT") (class "Default")
      (node (ref "J3") (pin "P$22") (pinfunction "BOOT_P$22") (pintype "bidirectional"))
      (node (ref "J3") (pin "P$9") (pinfunction "BOOT_P$9") (pintype "bidirectional"))
      (node (ref "JP3") (pin "6") (pinfunction "6_6") (pintype "passive"))
      (node (ref "R101") (pin "2") (pinfunction "2_2") (pintype "passive"))
      (node (ref "U$1") (pin "44") (pinfunction "PH3-BOOT0_44") (pintype "bidirectional"))
    )
    (net (code "13") (name "CAN_RX") (class "Default")
      (node (ref "CAN_RX") (pin "1") (pinfunction "TP_1") (pintype "input"))
      (node (ref "U$1") (pin "41") (pinfunction "PB5_41") (pintype "bidirectional"))
      (node (ref "U101") (pin "4") (pinfunction "RXD_4") (pintype "output"))
    )
    (net (code "14") (name "CAN_SILENT") (class "Default")
      (node (ref "CAN_SIL") (pin "1") (pinfunction "TP_1") (pintype "input"))
      (node (ref "U$1") (pin "40") (pinfunction "PB4_40") (pintype "bidirectional"))
      (node (ref "U101") (pin "8") (pinfunction "S_8") (pintype "input"))
    )
    (net (code "15") (name "CAN_TX") (class "Default")
      (node (ref "CAN_TX") (pin "1") (pinfunction "TP_1") (pintype "input"))
      (node (ref "U$1") (pin "42") (pinfunction "PB6_42") (pintype "bidirectional"))
      (node (ref "U101") (pin "1") (pinfunction "TXD_1") (pintype "input"))
    )
    (net (code "16") (name "DEBUG_1") (class "Default")
      (node (ref "DEBUG_1") (pin "1") (pinfunction "TP_1") (pintype "input"))
      (node (ref "JP1") (pin "1") (pinfunction "1_1") (pintype "passive"))
      (node (ref "LED4") (pin "A") (pinfunction "A_A") (pintype "passive"))
      (node (ref "U$1") (pin "18") (pinfunction "PB0_18") (pintype "bidirectional"))
    )
    (net (code "17") (name "DEBUG_2") (class "Default")
      (node (ref "DEBUG_2") (pin "1") (pinfunction "TP_1") (pintype "input"))
      (node (ref "JP1") (pin "2") (pinfunction "2_2") (pintype "passive"))
      (node (ref "LED3") (pin "A") (pinfunction "A_A") (pintype "passive"))
      (node (ref "U$1") (pin "17") (pinfunction "PA7_17") (pintype "bidirectional"))
    )
    (net (code "18") (name "GND") (class "Default")
      (node (ref "C101") (pin "2") (pinfunction "2_2") (pintype "passive"))
      (node (ref "C102") (pin "2") (pinfunction "2_2") (pintype "passive"))
      (node (ref "C103") (pin "2") (pinfunction "2_2") (pintype "passive"))
      (node (ref "C104") (pin "2") (pinfunction "2_2") (pintype "passive"))
      (node (ref "C105") (pin "2") (pinfunction "2_2") (pintype "passive"))
      (node (ref "C106") (pin "2") (pinfunction "2_2") (pintype "passive"))
      (node (ref "C107") (pin "2") (pinfunction "2_2") (pintype "passive"))
      (node (ref "C201") (pin "2") (pinfunction "2_2") (pintype "passive"))
      (node (ref "C202") (pin "2") (pinfunction "2_2") (pintype "passive"))
      (node (ref "C203") (pin "2") (pinfunction "2_2") (pintype "passive"))
      (node (ref "C301") (pin "2") (pinfunction "2_2") (pintype "passive"))
      (node (ref "C302") (pin "2") (pinfunction "2_2") (pintype "passive"))
      (node (ref "C303") (pin "2") (pinfunction "2_2") (pintype "passive"))
      (node (ref "C304") (pin "2") (pinfunction "2_2") (pintype "passive"))
      (node (ref "C305") (pin "2") (pinfunction "2_2") (pintype "passive"))
      (node (ref "C306") (pin "2") (pinfunction "2_2") (pintype "passive"))
      (node (ref "C307") (pin "2") (pinfunction "2_2") (pintype "passive"))
      (node (ref "C308") (pin "2") (pinfunction "2_2") (pintype "passive"))
      (node (ref "C310") (pin "2") (pinfunction "2_2") (pintype "passive"))
      (node (ref "C401") (pin "2") (pinfunction "2_2") (pintype "passive"))
      (node (ref "C402") (pin "2") (pinfunction "2_2") (pintype "passive"))
      (node (ref "C403") (pin "2") (pinfunction "2_2") (pintype "passive"))
      (node (ref "C404") (pin "2") (pinfunction "2_2") (pintype "passive"))
      (node (ref "C405") (pin "2") (pinfunction "2_2") (pintype "passive"))
      (node (ref "C406") (pin "2") (pinfunction "2_2") (pintype "passive"))
      (node (ref "C407") (pin "2") (pinfunction "2_2") (pintype "passive"))
      (node (ref "C408") (pin "2") (pinfunction "2_2") (pintype "passive"))
      (node (ref "C409") (pin "2") (pinfunction "2_2") (pintype "passive"))
      (node (ref "C410") (pin "2") (pinfunction "2_2") (pintype "passive"))
      (node (ref "J1") (pin "P$6") (pinfunction "GND_P$6") (pintype "passive"))
      (node (ref "J2") (pin "27") (pinfunction "27_27") (pintype "passive"))
      (node (ref "J2") (pin "28") (pinfunction "28_28") (pintype "passive"))
      (node (ref "J2") (pin "29") (pinfunction "29_29") (pintype "passive"))
      (node (ref "J2") (pin "30") (pinfunction "30_30") (pintype "passive"))
      (node (ref "J2") (pin "31") (pinfunction "31_31") (pintype "passive"))
      (node (ref "J2") (pin "32") (pinfunction "32_32") (pintype "passive"))
      (node (ref "J2") (pin "37") (pinfunction "37_37") (pintype "passive"))
      (node (ref "J2") (pin "38") (pinfunction "38_38") (pintype "passive"))
      (node (ref "J3") (pin "P$1") (pinfunction "GND_P$1") (pintype "bidirectional"))
      (node (ref "J3") (pin "P$14") (pinfunction "GND_P$14") (pintype "bidirectional"))
      (node (ref "J3") (pin "P$15") (pinfunction "GND_P$15") (pintype "bidirectional"))
      (node (ref "J3") (pin "P$16") (pinfunction "GND_P$16") (pintype "bidirectional"))
      (node (ref "J3") (pin "P$17") (pinfunction "GND_P$17") (pintype "bidirectional"))
      (node (ref "J3") (pin "P$2") (pinfunction "GND_P$2") (pintype "bidirectional"))
      (node (ref "J3") (pin "P$29") (pinfunction "GND_P$29") (pintype "bidirectional"))
      (node (ref "J3") (pin "P$30") (pinfunction "GND_P$30") (pintype "bidirectional"))
      (node (ref "JP2") (pin "2") (pinfunction "2_2") (pintype "passive"))
      (node (ref "JP2") (pin "4") (pinfunction "4_4") (pintype "passive"))
      (node (ref "JP3") (pin "9") (pinfunction "9_9") (pintype "passive"))
      (node (ref "R1") (pin "1") (pinfunction "1_1") (pintype "passive"))
      (node (ref "R101") (pin "1") (pinfunction "1_1") (pintype "passive"))
      (node (ref "R2") (pin "1") (pinfunction "1_1") (pintype "passive"))
      (node (ref "R202") (pin "1") (pinfunction "1_1") (pintype "passive"))
      (node (ref "R3") (pin "1") (pinfunction "1_1") (pintype "passive"))
      (node (ref "R305") (pin "1") (pinfunction "1_1") (pintype "passive"))
      (node (ref "R306") (pin "1") (pinfunction "1_1") (pintype "passive"))
      (node (ref "R308") (pin "1") (pinfunction "1_1") (pintype "passive"))
      (node (ref "R4") (pin "1") (pinfunction "1_1") (pintype "passive"))
      (node (ref "R406") (pin "2") (pinfunction "2_2") (pintype "passive"))
      (node (ref "R408") (pin "2") (pinfunction "2_2") (pintype "passive"))
      (node (ref "R411") (pin "2") (pinfunction "2_2") (pintype "passive"))
      (node (ref "R412") (pin "2") (pinfunction "2_2") (pintype "passive"))
      (node (ref "R414") (pin "1") (pinfunction "1_1") (pintype "passive"))
      (node (ref "R7") (pin "1") (pinfunction "1_1") (pintype "passive"))
      (node (ref "R8") (pin "1") (pinfunction "1_1") (pintype "passive"))
      (node (ref "R9") (pin "1") (pinfunction "1_1") (pintype "passive"))
      (node (ref "SWD1") (pin "GND") (pinfunction "GND_GND") (pintype "passive"))
      (node (ref "SWD1") (pin "GND@2") (pinfunction "GND_GND@2") (pintype "passive"))
      (node (ref "U$1") (pin "23") (pinfunction "VSS_23") (pintype "bidirectional"))
      (node (ref "U$1") (pin "35") (pinfunction "VSS_35") (pintype "bidirectional"))
      (node (ref "U$1") (pin "36") (pinfunction "VDDUSB_36") (pintype "bidirectional"))
      (node (ref "U$1") (pin "47") (pinfunction "VSS_47") (pintype "bidirectional"))
      (node (ref "U$1") (pin "8") (pinfunction "VSSA_8") (pintype "bidirectional"))
      (node (ref "U$1") (pin "EPAD") (pinfunction "VSS_EPAD") (pintype "bidirectional"))
      (node (ref "U101") (pin "2") (pinfunction "GND_2") (pintype "power_in"))
      (node (ref "U201") (pin "1") (pinfunction "GND_1") (pintype "power_in"))
      (node (ref "U201") (pin "11") (pinfunction "GND_11") (pintype "power_in"))
      (node (ref "U201") (pin "12") (pinfunction "GND_12") (pintype "power_in"))
      (node (ref "U201") (pin "16") (pinfunction "GND_16") (pintype "power_in"))
      (node (ref "U201") (pin "6") (pinfunction "LBO_6") (pintype "open_collector"))
      (node (ref "U201") (pin "7") (pinfunction "LBI_7") (pintype "input"))
      (node (ref "U201") (pin "9") (pinfunction "GND_9") (pintype "power_in"))
      (node (ref "U201") (pin "PAD") (pinfunction "GND_PAD") (pintype "power_in"))
      (node (ref "U300") (pin "7") (pinfunction "GND_7") (pintype "power_in"))
      (node (ref "U300") (pin "EPAD") (pinfunction "GND_EPAD") (pintype "power_in"))
      (node (ref "U301") (pin "2") (pinfunction "GND_2") (pintype "bidirectional"))
      (node (ref "U302") (pin "13") (pinfunction "GND_13") (pintype "power_in"))
      (node (ref "U302") (pin "5") (pinfunction "TEST_5") (pintype "power_in"))
      (node (ref "U400") (pin "15") (pinfunction "TEST0_15") (pintype "bidirectional"))
      (node (ref "U400") (pin "16") (pinfunction "TEST1_16") (pintype "bidirectional"))
      (node (ref "U400") (pin "7") (pinfunction "GND_7") (pintype "power_in"))
      (node (ref "U400") (pin "EPAD") (pinfunction "GND_EPAD") (pintype "power_in"))
      (node (ref "U401") (pin "2") (pinfunction "GND_2") (pintype "bidirectional"))
      (node (ref "X101") (pin "2") (pinfunction "SHIELD_2") (pintype "power_in"))
      (node (ref "X101") (pin "4") (pinfunction "SHIELD_4") (pintype "power_in"))
    )
    (net (code "19") (name "MAG_CURR_FDB") (class "Default")
      (node (ref "C411") (pin "1") (pinfunction "1_1") (pintype "passive"))
      (node (ref "MAG_CUR") (pin "1") (pinfunction "TP_1") (pintype "input"))
      (node (ref "R413") (pin "2") (pinfunction "2_2") (pintype "passive"))
      (node (ref "U$1") (pin "10") (pinfunction "PA0_10") (pintype "bidirectional"))
      (node (ref "U401") (pin "3") (pinfunction "OUT_3") (pintype "bidirectional"))
    )
    (net (code "20") (name "MAG_DIR") (class "Default")
      (node (ref "DIR") (pin "1") (pinfunction "TP_1") (pintype "input"))
      (node (ref "R403") (pin "2") (pinfunction "2_2") (pintype "passive"))
      (node (ref "U$1") (pin "39") (pinfunction "PB3_39") (pintype "bidirectional"))
    )
    (net (code "21") (name "MAG_EN") (class "Default")
      (node (ref "ENABLE_") (pin "1") (pinfunction "TP_1") (pintype "input"))
      (node (ref "R402") (pin "2") (pinfunction "2_2") (pintype "passive"))
      (node (ref "U$1") (pin "46") (pinfunction "PB9_46") (pintype "bidirectional"))
    )
    (net (code "22") (name "MAG_FAULT") (class "Default")
      (node (ref "C405") (pin "1") (pinfunction "1_1") (pintype "passive"))
      (node (ref "FAULT_") (pin "1") (pinfunction "TP_1") (pintype "input"))
      (node (ref "R402") (pin "1") (pinfunction "1_1") (pintype "passive"))
      (node (ref "U$1") (pin "45") (pinfunction "PB8_45") (pintype "bidirectional"))
      (node (ref "U400") (pin "13") (pinfunction "EN/FAULT_13") (pintype "bidirectional"))
    )
    (net (code "23") (name "MAG_PWM") (class "Default")
      (node (ref "PWM") (pin "1") (pinfunction "TP_1") (pintype "input"))
      (node (ref "R404") (pin "2") (pinfunction "2_2") (pintype "passive"))
      (node (ref "U$1") (pin "38") (pinfunction "PA15_38") (pintype "bidirectional"))
    )
    (net (code "24") (name "MAG_STBY") (class "Default")
      (node (ref "C404") (pin "1") (pinfunction "1_1") (pintype "passive"))
      (node (ref "R401") (pin "2") (pinfunction "2_2") (pintype "passive"))
      (node (ref "STBY_") (pin "1") (pinfunction "TP_1") (pintype "input"))
      (node (ref "U$1") (pin "43") (pinfunction "PB7_43") (pintype "bidirectional"))
      (node (ref "U400") (pin "14") (pinfunction "STBY/RESET_14") (pintype "bidirectional"))
    )
    (net (code "25") (name "NRST") (class "Default")
      (node (ref "C106") (pin "1") (pinfunction "1_1") (pintype "passive"))
      (node (ref "SWD1") (pin "!RESET") (pinfunction "~{RESET}_!RESET") (pintype "passive"))
      (node (ref "U$1") (pin "7") (pinfunction "NRST_7") (pintype "bidirectional"))
    )
    (net (code "26") (name "Net-(ADDR_0-TP)") (class "Default")
      (node (ref "ADDR_0") (pin "1") (pinfunction "TP_1") (pintype "input"))
      (node (ref "JP2") (pin "1") (pinfunction "1_1") (pintype "passive"))
      (node (ref "U$1") (pin "19") (pinfunction "PB1_19") (pintype "bidirectional"))
    )
    (net (code "27") (name "Net-(ADDR_1-TP)") (class "Default")
      (node (ref "ADDR_1") (pin "1") (pinfunction "TP_1") (pintype "input"))
      (node (ref "JP2") (pin "3") (pinfunction "3_3") (pintype "passive"))
      (node (ref "U$1") (pin "20") (pinfunction "PB2_20") (pintype "bidirectional"))
    )
    (net (code "28") (name "Net-(C407-Pad1)") (class "Default")
      (node (ref "C407") (pin "1") (pinfunction "1_1") (pintype "passive"))
      (node (ref "R407") (pin "2") (pinfunction "2_2") (pintype "passive"))
    )
    (net (code "29") (name "Net-(I2C_SCL-TP)") (class "Default")
      (node (ref "I2C_SCL") (pin "1") (pinfunction "TP_1") (pintype "input"))
      (node (ref "J3") (pin "P$24") (pinfunction "I2C_SCL_P$24") (pintype "bidirectional"))
      (node (ref "J3") (pin "P$7") (pinfunction "I2C_SCL_P$7") (pintype "bidirectional"))
      (node (ref "JP3") (pin "4") (pinfunction "4_4") (pintype "passive"))
      (node (ref "R105") (pin "1") (pinfunction "1_1") (pintype "passive"))
      (node (ref "U$1") (pin "21") (pinfunction "PB10_21") (pintype "bidirectional"))
    )
    (net (code "30") (name "Net-(I2C_SDA-TP)") (class "Default")
      (node (ref "I2C_SDA") (pin "1") (pinfunction "TP_1") (pintype "input"))
      (node (ref "J3") (pin "P$23") (pinfunction "I2C_SDA_P$23") (pintype "bidirectional"))
      (node (ref "J3") (pin "P$8") (pinfunction "I2C_SDA_P$8") (pintype "bidirectional"))
      (node (ref "JP3") (pin "5") (pinfunction "5_5") (pintype "passive"))
      (node (ref "R106") (pin "1") (pinfunction "1_1") (pintype "passive"))
      (node (ref "U$1") (pin "22") (pinfunction "PB11_22") (pintype "bidirectional"))
    )
    (net (code "31") (name "Net-(J301-Pad1)") (class "Default")
      (node (ref "J301") (pin "1") (pinfunction "1_1") (pintype "passive"))
      (node (ref "J301") (pin "2") (pinfunction "2_2") (pintype "passive"))
    )
    (net (code "32") (name "Net-(J301-Pad3)") (class "Default")
      (node (ref "J301") (pin "3") (pinfunction "3_3") (pintype "passive"))
      (node (ref "J301") (pin "4") (pinfunction "4_4") (pintype "passive"))
    )
    (net (code "33") (name "Net-(J301-Pad5)") (class "Default")
      (node (ref "J301") (pin "5") (pinfunction "5_5") (pintype "passive"))
      (node (ref "J301") (pin "6") (pinfunction "6_6") (pintype "passive"))
    )
    (net (code "34") (name "Net-(L201-Pad1)") (class "Default")
      (node (ref "L201") (pin "1") (pinfunction "1_1") (pintype "passive"))
      (node (ref "U201") (pin "14") (pinfunction "SW_14") (pintype "output"))
      (node (ref "U201") (pin "15") (pinfunction "SW_15") (pintype "output"))
    )
    (net (code "35") (name "Net-(LED1-PadC)") (class "Default")
      (node (ref "LED1") (pin "C") (pinfunction "C_C") (pintype "passive"))
      (node (ref "R1") (pin "2") (pinfunction "2_2") (pintype "passive"))
    )
    (net (code "36") (name "Net-(LED2-PadC)") (class "Default")
      (node (ref "LED2") (pin "C") (pinfunction "C_C") (pintype "passive"))
      (node (ref "R2") (pin "2") (pinfunction "2_2") (pintype "passive"))
    )
    (net (code "37") (name "Net-(LED3-PadC)") (class "Default")
      (node (ref "LED3") (pin "C") (pinfunction "C_C") (pintype "passive"))
      (node (ref "R3") (pin "2") (pinfunction "2_2") (pintype "passive"))
    )
    (net (code "38") (name "Net-(LED4-PadC)") (class "Default")
      (node (ref "LED4") (pin "C") (pinfunction "C_C") (pintype "passive"))
      (node (ref "R4") (pin "2") (pinfunction "2_2") (pintype "passive"))
    )
    (net (code "39") (name "Net-(LED301-BA)") (class "Default")
      (node (ref "J302") (pin "6") (pinfunction "6_6") (pintype "passive"))
      (node (ref "LED301") (pin "P$6") (pinfunction "BA_P$6") (pintype "bidirectional"))
    )
    (net (code "40") (name "Net-(LED301-BC)") (class "Default")
      (node (ref "LED301") (pin "P$1") (pinfunction "BC_P$1") (pintype "bidirectional"))
      (node (ref "R7") (pin "2") (pinfunction "2_2") (pintype "passive"))
    )
    (net (code "41") (name "Net-(LED301-GA)") (class "Default")
      (node (ref "J302") (pin "4") (pinfunction "4_4") (pintype "passive"))
      (node (ref "LED301") (pin "P$5") (pinfunction "GA_P$5") (pintype "bidirectional"))
    )
    (net (code "42") (name "Net-(LED301-GC)") (class "Default")
      (node (ref "LED301") (pin "P$2") (pinfunction "GC_P$2") (pintype "bidirectional"))
      (node (ref "R8") (pin "2") (pinfunction "2_2") (pintype "passive"))
    )
    (net (code "43") (name "Net-(LED301-RA)") (class "Default")
      (node (ref "J302") (pin "2") (pinfunction "2_2") (pintype "passive"))
      (node (ref "LED301") (pin "P$4") (pinfunction "RA_P$4") (pintype "bidirectional"))
    )
    (net (code "44") (name "Net-(LED301-RC)") (class "Default")
      (node (ref "LED301") (pin "P$3") (pinfunction "RC_P$3") (pintype "bidirectional"))
      (node (ref "R9") (pin "2") (pinfunction "2_2") (pintype "passive"))
    )
    (net (code "45") (name "Net-(U$1-PH0-OSC_IN)") (class "Default")
      (node (ref "C104") (pin "1") (pinfunction "1_1") (pintype "passive"))
      (node (ref "U$1") (pin "5") (pinfunction "PH0-OSC_IN_5") (pintype "bidirectional"))
      (node (ref "X101") (pin "3") (pinfunction "2_3") (pintype "passive"))
    )
    (net (code "46") (name "Net-(U$1-PH1-OSC_OUT)") (class "Default")
      (node (ref "C105") (pin "1") (pinfunction "1_1") (pintype "passive"))
      (node (ref "U$1") (pin "6") (pinfunction "PH1-OSC_OUT_6") (pintype "bidirectional"))
      (node (ref "X101") (pin "1") (pinfunction "1_1") (pintype "passive"))
    )
    (net (code "47") (name "Net-(U101-CANH)") (class "Default")
      (node (ref "J2") (pin "17") (pinfunction "17_17") (pintype "passive"))
      (node (ref "J2") (pin "18") (pinfunction "18_18") (pintype "passive"))
      (node (ref "J3") (pin "P$25") (pinfunction "CAN_H_P$25") (pintype "bidirectional"))
      (node (ref "J3") (pin "P$6") (pinfunction "CAN_H_P$6") (pintype "bidirectional"))
      (node (ref "JP3") (pin "3") (pinfunction "3_3") (pintype "passive"))
      (node (ref "U101") (pin "7") (pinfunction "CANH_7") (pintype "bidirectional"))
    )
    (net (code "48") (name "Net-(U101-CANL)") (class "Default")
      (node (ref "J2") (pin "19") (pinfunction "19_19") (pintype "passive"))
      (node (ref "J2") (pin "20") (pinfunction "20_20") (pintype "passive"))
      (node (ref "J3") (pin "P$26") (pinfunction "CAN_L_P$26") (pintype "bidirectional"))
      (node (ref "J3") (pin "P$5") (pinfunction "CAN_L_P$5") (pintype "bidirectional"))
      (node (ref "JP3") (pin "2") (pinfunction "2_2") (pintype "passive"))
      (node (ref "U101") (pin "6") (pinfunction "CANL_6") (pintype "bidirectional"))
    )
    (net (code "49") (name "Net-(U201-PG)") (class "Default")
      (node (ref "PG") (pin "1") (pinfunction "1_1") (pintype "passive"))
      (node (ref "U201") (pin "13") (pinfunction "PG_13") (pintype "open_collector"))
    )
    (net (code "50") (name "Net-(U201-SYNC)") (class "Default")
      (node (ref "R201") (pin "1") (pinfunction "1_1") (pintype "passive"))
      (node (ref "R202") (pin "2") (pinfunction "2_2") (pintype "passive"))
      (node (ref "SYNC") (pin "1") (pinfunction "1_1") (pintype "passive"))
      (node (ref "U201") (pin "5") (pinfunction "SYNC_5") (pintype "input"))
    )
    (net (code "51") (name "Net-(U300-OUTU)") (class "Default")
      (node (ref "J302") (pin "1") (pinfunction "1_1") (pintype "passive"))
      (node (ref "U300") (pin "3") (pinfunction "OUTU_3") (pintype "output"))
    )
    (net (code "52") (name "Net-(U300-OUTV)") (class "Default")
      (node (ref "J302") (pin "3") (pinfunction "3_3") (pintype "passive"))
      (node (ref "U300") (pin "8") (pinfunction "OUTV_8") (pintype "output"))
    )
    (net (code "53") (name "Net-(U300-OUTW)") (class "Default")
      (node (ref "J302") (pin "5") (pinfunction "5_5") (pintype "passive"))
      (node (ref "U300") (pin "10") (pinfunction "OUTW_10") (pintype "output"))
    )
    (net (code "54") (name "Net-(U300-SENSEU)") (class "Default")
      (node (ref "R304") (pin "1") (pinfunction "1_1") (pintype "passive"))
      (node (ref "R305") (pin "2") (pinfunction "2_2") (pintype "passive"))
      (node (ref "R306") (pin "2") (pinfunction "2_2") (pintype "passive"))
      (node (ref "U300") (pin "4") (pinfunction "SENSEU_4") (pintype "output"))
      (node (ref "U300") (pin "9") (pinfunction "SENSEVW_9") (pintype "output"))
    )
    (net (code "55") (name "Net-(U301-IN+)") (class "Default")
      (node (ref "C308") (pin "1") (pinfunction "1_1") (pintype "passive"))
      (node (ref "R303") (pin "1") (pinfunction "1_1") (pintype "passive"))
      (node (ref "R304") (pin "2") (pinfunction "2_2") (pintype "passive"))
      (node (ref "U301") (pin "1") (pinfunction "IN+_1") (pintype "bidirectional"))
    )
    (net (code "56") (name "Net-(U301-IN-)") (class "Default")
      (node (ref "C309") (pin "2") (pinfunction "2_2") (pintype "passive"))
      (node (ref "R307") (pin "1") (pinfunction "1_1") (pintype "passive"))
      (node (ref "R308") (pin "2") (pinfunction "2_2") (pintype "passive"))
      (node (ref "U301") (pin "5") (pinfunction "IN-_5") (pintype "bidirectional"))
    )
    (net (code "57") (name "Net-(U302-MOSI)") (class "Default")
      (node (ref "R309") (pin "2") (pinfunction "2_2") (pintype "passive"))
      (node (ref "U302") (pin "4") (pinfunction "MOSI_4") (pintype "input"))
    )
    (net (code "58") (name "Net-(U400-PH)") (class "Default")
      (node (ref "R403") (pin "1") (pinfunction "1_1") (pintype "passive"))
      (node (ref "U400") (pin "1") (pinfunction "PH_1") (pintype "input"))
    )
    (net (code "59") (name "Net-(U400-PWM)") (class "Default")
      (node (ref "R404") (pin "1") (pinfunction "1_1") (pintype "passive"))
      (node (ref "U400") (pin "2") (pinfunction "PWM_2") (pintype "input"))
    )
    (net (code "60") (name "Net-(U400-REF)") (class "Default")
      (node (ref "C406") (pin "1") (pinfunction "1_1") (pintype "passive"))
      (node (ref "R405") (pin "2") (pinfunction "2_2") (pintype "passive"))
      (node (ref "R406") (pin "1") (pinfunction "1_1") (pintype "passive"))
      (node (ref "U400") (pin "11") (pinfunction "REF_11") (pintype "passive"))
    )
    (net (code "61") (name "Net-(U400-SENSEA)") (class "Default")
      (node (ref "R410") (pin "1") (pinfunction "1_1") (pintype "passive"))
      (node (ref "R411") (pin "1") (pinfunction "1_1") (pintype "passive"))
      (node (ref "R412") (pin "1") (pinfunction "1_1") (pintype "passive"))
      (node (ref "U400") (pin "4") (pinfunction "SENSEA_4") (pintype "output"))
      (node (ref "U400") (pin "9") (pinfunction "SENSEB_9") (pintype "output"))
    )
    (net (code "62") (name "Net-(U400-TOFF)") (class "Default")
      (node (ref "R407") (pin "1") (pinfunction "1_1") (pintype "passive"))
      (node (ref "R408") (pin "1") (pinfunction "1_1") (pintype "passive"))
      (node (ref "U400") (pin "12") (pinfunction "TOFF_12") (pintype "passive"))
    )
    (net (code "63") (name "Net-(U401-IN+)") (class "Default")
      (node (ref "C410") (pin "1") (pinfunction "1_1") (pintype "passive"))
      (node (ref "R409") (pin "1") (pinfunction "1_1") (pintype "passive"))
      (node (ref "R410") (pin "2") (pinfunction "2_2") (pintype "passive"))
      (node (ref "U401") (pin "1") (pinfunction "IN+_1") (pintype "bidirectional"))
    )
    (net (code "64") (name "Net-(U401-IN-)") (class "Default")
      (node (ref "C411") (pin "2") (pinfunction "2_2") (pintype "passive"))
      (node (ref "R413") (pin "1") (pinfunction "1_1") (pintype "passive"))
      (node (ref "R414") (pin "2") (pinfunction "2_2") (pintype "passive"))
      (node (ref "U401") (pin "5") (pinfunction "IN-_5") (pintype "bidirectional"))
    )
    (net (code "65") (name "OUT1") (class "Default")
      (node (ref "J3") (pin "P$10") (pinfunction "MAG_1_P$10") (pintype "bidirectional"))
      (node (ref "J3") (pin "P$21") (pinfunction "MAG_1_P$21") (pintype "bidirectional"))
      (node (ref "JP3") (pin "7") (pinfunction "7_7") (pintype "passive"))
      (node (ref "U400") (pin "10") (pinfunction "OUTB1_10") (pintype "output"))
      (node (ref "U400") (pin "3") (pinfunction "OUTA1_3") (pintype "output"))
    )
    (net (code "66") (name "OUT2") (class "Default")
      (node (ref "J3") (pin "P$11") (pinfunction "MAG_2_P$11") (pintype "bidirectional"))
      (node (ref "J3") (pin "P$20") (pinfunction "MAG_2_P$20") (pintype "bidirectional"))
      (node (ref "JP3") (pin "8") (pinfunction "8_8") (pintype "passive"))
      (node (ref "U400") (pin "5") (pinfunction "OUTA2_5") (pintype "output"))
      (node (ref "U400") (pin "8") (pinfunction "OUTB2_8") (pintype "output"))
    )
    (net (code "67") (name "SPI1_CS") (class "Default")
      (node (ref "SPI_CS") (pin "1") (pinfunction "TP_1") (pintype "input"))
      (node (ref "U$1") (pin "14") (pinfunction "PA4_14") (pintype "bidirectional"))
      (node (ref "U302") (pin "1") (pinfunction "CSN_1") (pintype "input"))
    )
    (net (code "68") (name "SPI1_MISO") (class "Default")
      (node (ref "SPI_MISO") (pin "1") (pinfunction "TP_1") (pintype "input"))
      (node (ref "U$1") (pin "16") (pinfunction "PA6_16") (pintype "bidirectional"))
      (node (ref "U302") (pin "3") (pinfunction "MISO_3") (pintype "output"))
    )
    (net (code "69") (name "SPI1_SCK") (class "Default")
      (node (ref "SPI_SCK") (pin "1") (pinfunction "TP_1") (pintype "input"))
      (node (ref "U$1") (pin "15") (pinfunction "PA5_15") (pintype "bidirectional"))
      (node (ref "U302") (pin "2") (pinfunction "SCLK_2") (pintype "input"))
    )
    (net (code "70") (name "SWCLK") (class "Default")
      (node (ref "SWD1") (pin "SWDCLK") (pinfunction "SWDCLK/TCK_SWDCLK") (pintype "passive"))
      (node (ref "U$1") (pin "37") (pinfunction "PA14_37") (pintype "bidirectional"))
    )
    (net (code "71") (name "SWDIO") (class "Default")
      (node (ref "SWD1") (pin "SWDIO") (pinfunction "SWDIO/TMS_SWDIO") (pintype "passive"))
      (node (ref "U$1") (pin "34") (pinfunction "PA13_34") (pintype "bidirectional"))
    )
    (net (code "72") (name "UART_RX") (class "Default")
      (node (ref "R104") (pin "2") (pinfunction "2_2") (pintype "passive"))
      (node (ref "U$1") (pin "13") (pinfunction "PA3_13") (pintype "bidirectional"))
    )
    (net (code "73") (name "UART_RX1") (class "Default")
      (node (ref "J1") (pin "P$3") (pinfunction "RXI_P$3") (pintype "passive"))
      (node (ref "R104") (pin "1") (pinfunction "1_1") (pintype "passive"))
    )
    (net (code "74") (name "UART_TX") (class "Default")
      (node (ref "J1") (pin "P$2") (pinfunction "TXO_P$2") (pintype "passive"))
      (node (ref "U$1") (pin "12") (pinfunction "PA2_12") (pintype "bidirectional"))
    )
    (net (code "75") (name "VBUSP") (class "Default")
      (node (ref "C201") (pin "1") (pinfunction "1_1") (pintype "passive"))
      (node (ref "C202") (pin "1") (pinfunction "1_1") (pintype "passive"))
      (node (ref "C301") (pin "1") (pinfunction "1_1") (pintype "passive"))
      (node (ref "C302") (pin "1") (pinfunction "1_1") (pintype "passive"))
      (node (ref "C303") (pin "1") (pinfunction "1_1") (pintype "passive"))
      (node (ref "C401") (pin "1") (pinfunction "1_1") (pintype "passive"))
      (node (ref "C402") (pin "1") (pinfunction "1_1") (pintype "passive"))
      (node (ref "C403") (pin "1") (pinfunction "1_1") (pintype "passive"))
      (node (ref "J1") (pin "P$4") (pinfunction "VCC_P$4") (pintype "passive"))
      (node (ref "J2") (pin "21") (pinfunction "21_21") (pintype "passive"))
      (node (ref "J2") (pin "22") (pinfunction "22_22") (pintype "passive"))
      (node (ref "J2") (pin "23") (pinfunction "23_23") (pintype "passive"))
      (node (ref "J2") (pin "24") (pinfunction "24_24") (pintype "passive"))
      (node (ref "J2") (pin "25") (pinfunction "25_25") (pintype "passive"))
      (node (ref "J2") (pin "26") (pinfunction "26_26") (pintype "passive"))
      (node (ref "J3") (pin "P$12") (pinfunction "VCC_P$12") (pintype "bidirectional"))
      (node (ref "J3") (pin "P$13") (pinfunction "VCC_P$13") (pintype "bidirectional"))
      (node (ref "J3") (pin "P$18") (pinfunction "VCC_P$18") (pintype "bidirectional"))
      (node (ref "J3") (pin "P$19") (pinfunction "VCC_P$19") (pintype "bidirectional"))
      (node (ref "J3") (pin "P$27") (pinfunction "VCC_P$27") (pintype "bidirectional"))
      (node (ref "J3") (pin "P$28") (pinfunction "VCC_P$28") (pintype "bidirectional"))
      (node (ref "J3") (pin "P$3") (pinfunction "VCC_P$3") (pintype "bidirectional"))
      (node (ref "J3") (pin "P$4") (pinfunction "VCC_P$4") (pintype "bidirectional"))
      (node (ref "JP3") (pin "1") (pinfunction "1_1") (pintype "passive"))
      (node (ref "LED1") (pin "A") (pinfunction "A_A") (pintype "passive"))
      (node (ref "R201") (pin "2") (pinfunction "2_2") (pintype "passive"))
      (node (ref "U201") (pin "2") (pinfunction "VIN_2") (pintype "power_in"))
      (node (ref "U201") (pin "3") (pinfunction "VIN_3") (pintype "power_in"))
      (node (ref "U201") (pin "4") (pinfunction "EN_4") (pintype "input"))
      (node (ref "U201") (pin "8") (pinfunction "VIN_8") (pintype "power_in"))
      (node (ref "U300") (pin "6") (pinfunction "VS_6") (pintype "power_in"))
      (node (ref "U400") (pin "6") (pinfunction "VS_6") (pintype "power_in"))
      (node (ref "VBUSP") (pin "1") (pinfunction "1_1") (pintype "passive"))
    )
    (net (code "76") (name "unconnected-(J1-CTS-PadP$5)") (class "Default")
      (node (ref "J1") (pin "P$5") (pinfunction "CTS_P$5") (pintype "passive"))
    )
    (net (code "77") (name "unconnected-(J1-DTR-PadP$1)") (class "Default")
      (node (ref "J1") (pin "P$1") (pinfunction "DTR_P$1") (pintype "passive"))
    )
    (net (code "78") (name "unconnected-(J2-Pad1)") (class "Default")
      (node (ref "J2") (pin "1") (pinfunction "1_1") (pintype "passive"))
    )
    (net (code "79") (name "unconnected-(J2-Pad2)") (class "Default")
      (node (ref "J2") (pin "2") (pinfunction "2_2") (pintype "passive"))
    )
    (net (code "80") (name "unconnected-(J2-Pad3)") (class "Default")
      (node (ref "J2") (pin "3") (pinfunction "3_3") (pintype "passive"))
    )
    (net (code "81") (name "unconnected-(J2-Pad4)") (class "Default")
      (node (ref "J2") (pin "4") (pinfunction "4_4") (pintype "passive"))
    )
    (net (code "82") (name "unconnected-(J2-Pad5)") (class "Default")
      (node (ref "J2") (pin "5") (pinfunction "5_5") (pintype "passive"))
    )
    (net (code "83") (name "unconnected-(J2-Pad6)") (class "Default")
      (node (ref "J2") (pin "6") (pinfunction "6_6") (pintype "passive"))
    )
    (net (code "84") (name "unconnected-(J2-Pad7)") (class "Default")
      (node (ref "J2") (pin "7") (pinfunction "7_7") (pintype "passive"))
    )
    (net (code "85") (name "unconnected-(J2-Pad8)") (class "Default")
      (node (ref "J2") (pin "8") (pinfunction "8_8") (pintype "passive"))
    )
    (net (code "86") (name "unconnected-(J2-Pad9)") (class "Default")
      (node (ref "J2") (pin "9") (pinfunction "9_9") (pintype "passive"))
    )
    (net (code "87") (name "unconnected-(J2-Pad10)") (class "Default")
      (node (ref "J2") (pin "10") (pinfunction "10_10") (pintype "passive"))
    )
    (net (code "88") (name "unconnected-(J2-Pad11)") (class "Default")
      (node (ref "J2") (pin "11") (pinfunction "11_11") (pintype "passive"))
    )
    (net (code "89") (name "unconnected-(J2-Pad12)") (class "Default")
      (node (ref "J2") (pin "12") (pinfunction "12_12") (pintype "passive"))
    )
    (net (code "90") (name "unconnected-(J2-Pad13)") (class "Default")
      (node (ref "J2") (pin "13") (pinfunction "13_13") (pintype "passive"))
    )
    (net (code "91") (name "unconnected-(J2-Pad14)") (class "Default")
      (node (ref "J2") (pin "14") (pinfunction "14_14") (pintype "passive"))
    )
    (net (code "92") (name "unconnected-(J2-Pad15)") (class "Default")
      (node (ref "J2") (pin "15") (pinfunction "15_15") (pintype "passive"))
    )
    (net (code "93") (name "unconnected-(J2-Pad16)") (class "Default")
      (node (ref "J2") (pin "16") (pinfunction "16_16") (pintype "passive"))
    )
    (net (code "94") (name "unconnected-(J2-Pad33)") (class "Default")
      (node (ref "J2") (pin "33") (pinfunction "33_33") (pintype "passive"))
    )
    (net (code "95") (name "unconnected-(J2-Pad34)") (class "Default")
      (node (ref "J2") (pin "34") (pinfunction "34_34") (pintype "passive"))
    )
    (net (code "96") (name "unconnected-(J2-Pad35)") (class "Default")
      (node (ref "J2") (pin "35") (pinfunction "35_35") (pintype "passive"))
    )
    (net (code "97") (name "unconnected-(J2-Pad36)") (class "Default")
      (node (ref "J2") (pin "36") (pinfunction "36_36") (pintype "passive"))
    )
    (net (code "98") (name "unconnected-(J2-Pad39)") (class "Default")
      (node (ref "J2") (pin "39") (pinfunction "39_39") (pintype "passive"))
    )
    (net (code "99") (name "unconnected-(J2-Pad40)") (class "Default")
      (node (ref "J2") (pin "40") (pinfunction "40_40") (pintype "passive"))
    )
    (net (code "100") (name "unconnected-(SWD1-NC{slash}TDI-PadNC)") (class "Default")
      (node (ref "SWD1") (pin "NC") (pinfunction "NC/TDI_NC") (pintype "passive"))
    )
    (net (code "101") (name "unconnected-(SWD1-PadGNDDET)") (class "Default")
      (node (ref "SWD1") (pin "GNDDET") (pinfunction "GNDDET_GNDDET") (pintype "passive"))
    )
    (net (code "102") (name "unconnected-(SWD1-SWO{slash}TDO-PadSWO)") (class "Default")
      (node (ref "SWD1") (pin "SWO") (pinfunction "SWO/TDO_SWO") (pintype "passive"))
    )
    (net (code "103") (name "unconnected-(U$1-PC13-Pad2)") (class "Default")
      (node (ref "U$1") (pin "2") (pinfunction "PC13_2") (pintype "bidirectional"))
    )
    (net (code "104") (name "unconnected-(U$1-PC14-OSC32_IN-Pad3)") (class "Default")
      (node (ref "U$1") (pin "3") (pinfunction "PC14-OSC32_IN_3") (pintype "bidirectional"))
    )
    (net (code "105") (name "unconnected-(U$1-PC15-OSC32_OUT-Pad4)") (class "Default")
      (node (ref "U$1") (pin "4") (pinfunction "PC15-OSC32_OUT_4") (pintype "bidirectional"))
    )
    (net (code "106") (name "unconnected-(U101-SHDN-Pad5)") (class "Default")
      (node (ref "U101") (pin "5") (pinfunction "SHDN_5") (pintype "input"))
    )
    (net (code "107") (name "unconnected-(U302-A-Pad7)") (class "Default")
      (node (ref "U302") (pin "7") (pinfunction "A_7") (pintype "output"))
    )
    (net (code "108") (name "unconnected-(U302-B-Pad6)") (class "Default")
      (node (ref "U302") (pin "6") (pinfunction "B_6") (pintype "output"))
    )
    (net (code "109") (name "unconnected-(U302-I{slash}PWM-Pad14)") (class "Default")
      (node (ref "U302") (pin "14") (pinfunction "I/PWM_14") (pintype "output"))
    )
    (net (code "110") (name "unconnected-(U302-U-Pad10)") (class "Default")
      (node (ref "U302") (pin "10") (pinfunction "U_10") (pintype "output"))
    )
    (net (code "111") (name "unconnected-(U302-V-Pad9)") (class "Default")
      (node (ref "U302") (pin "9") (pinfunction "V_9") (pintype "output"))
    )
    (net (code "112") (name "unconnected-(U302-W{slash}PWM-Pad8)") (class "Default")
      (node (ref "U302") (pin "8") (pinfunction "W/PWM_8") (pintype "output"))
    )
  )
)
